# Sheet1.net
KiCad netlist of a schematic drawn in Altium Designer
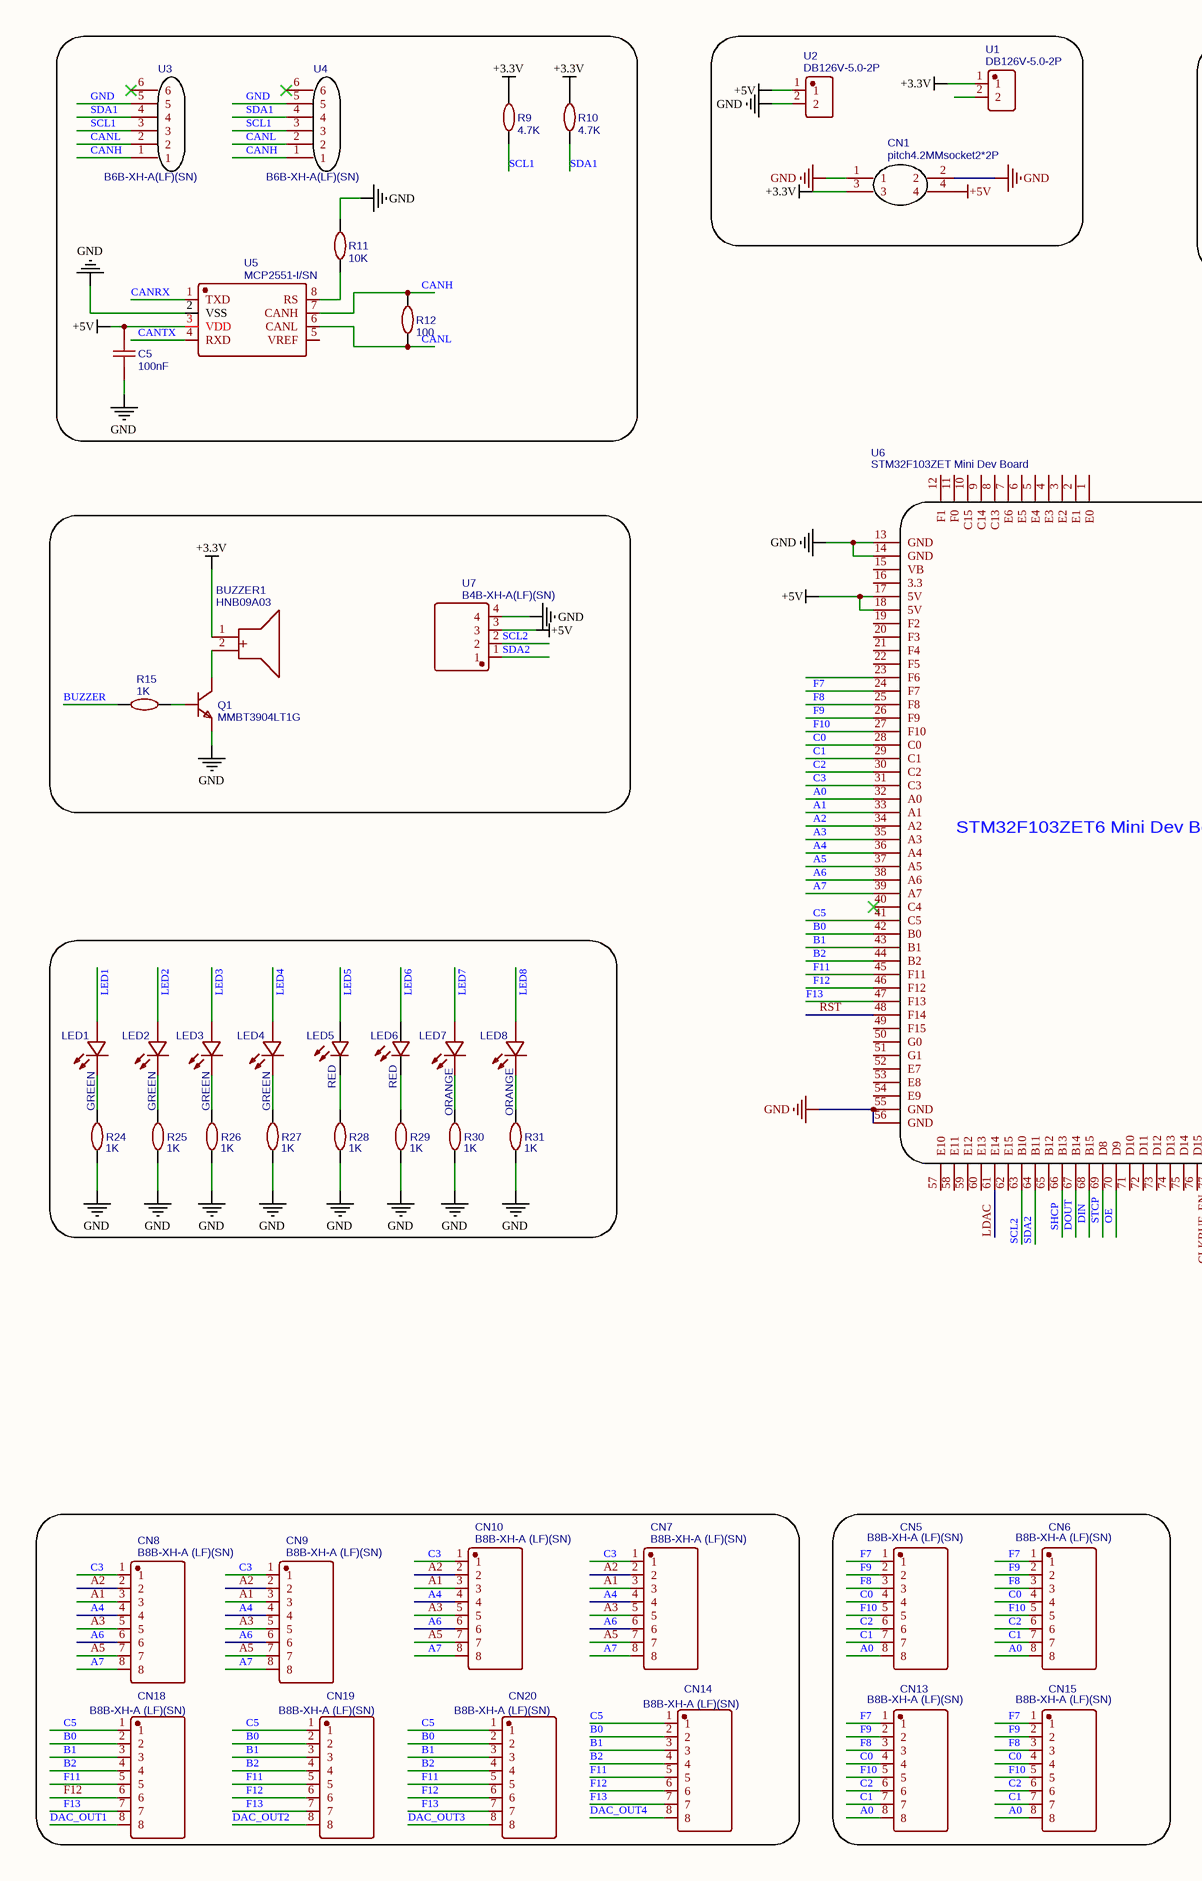
[diagram p0: Sheet1.SchDoc, left]
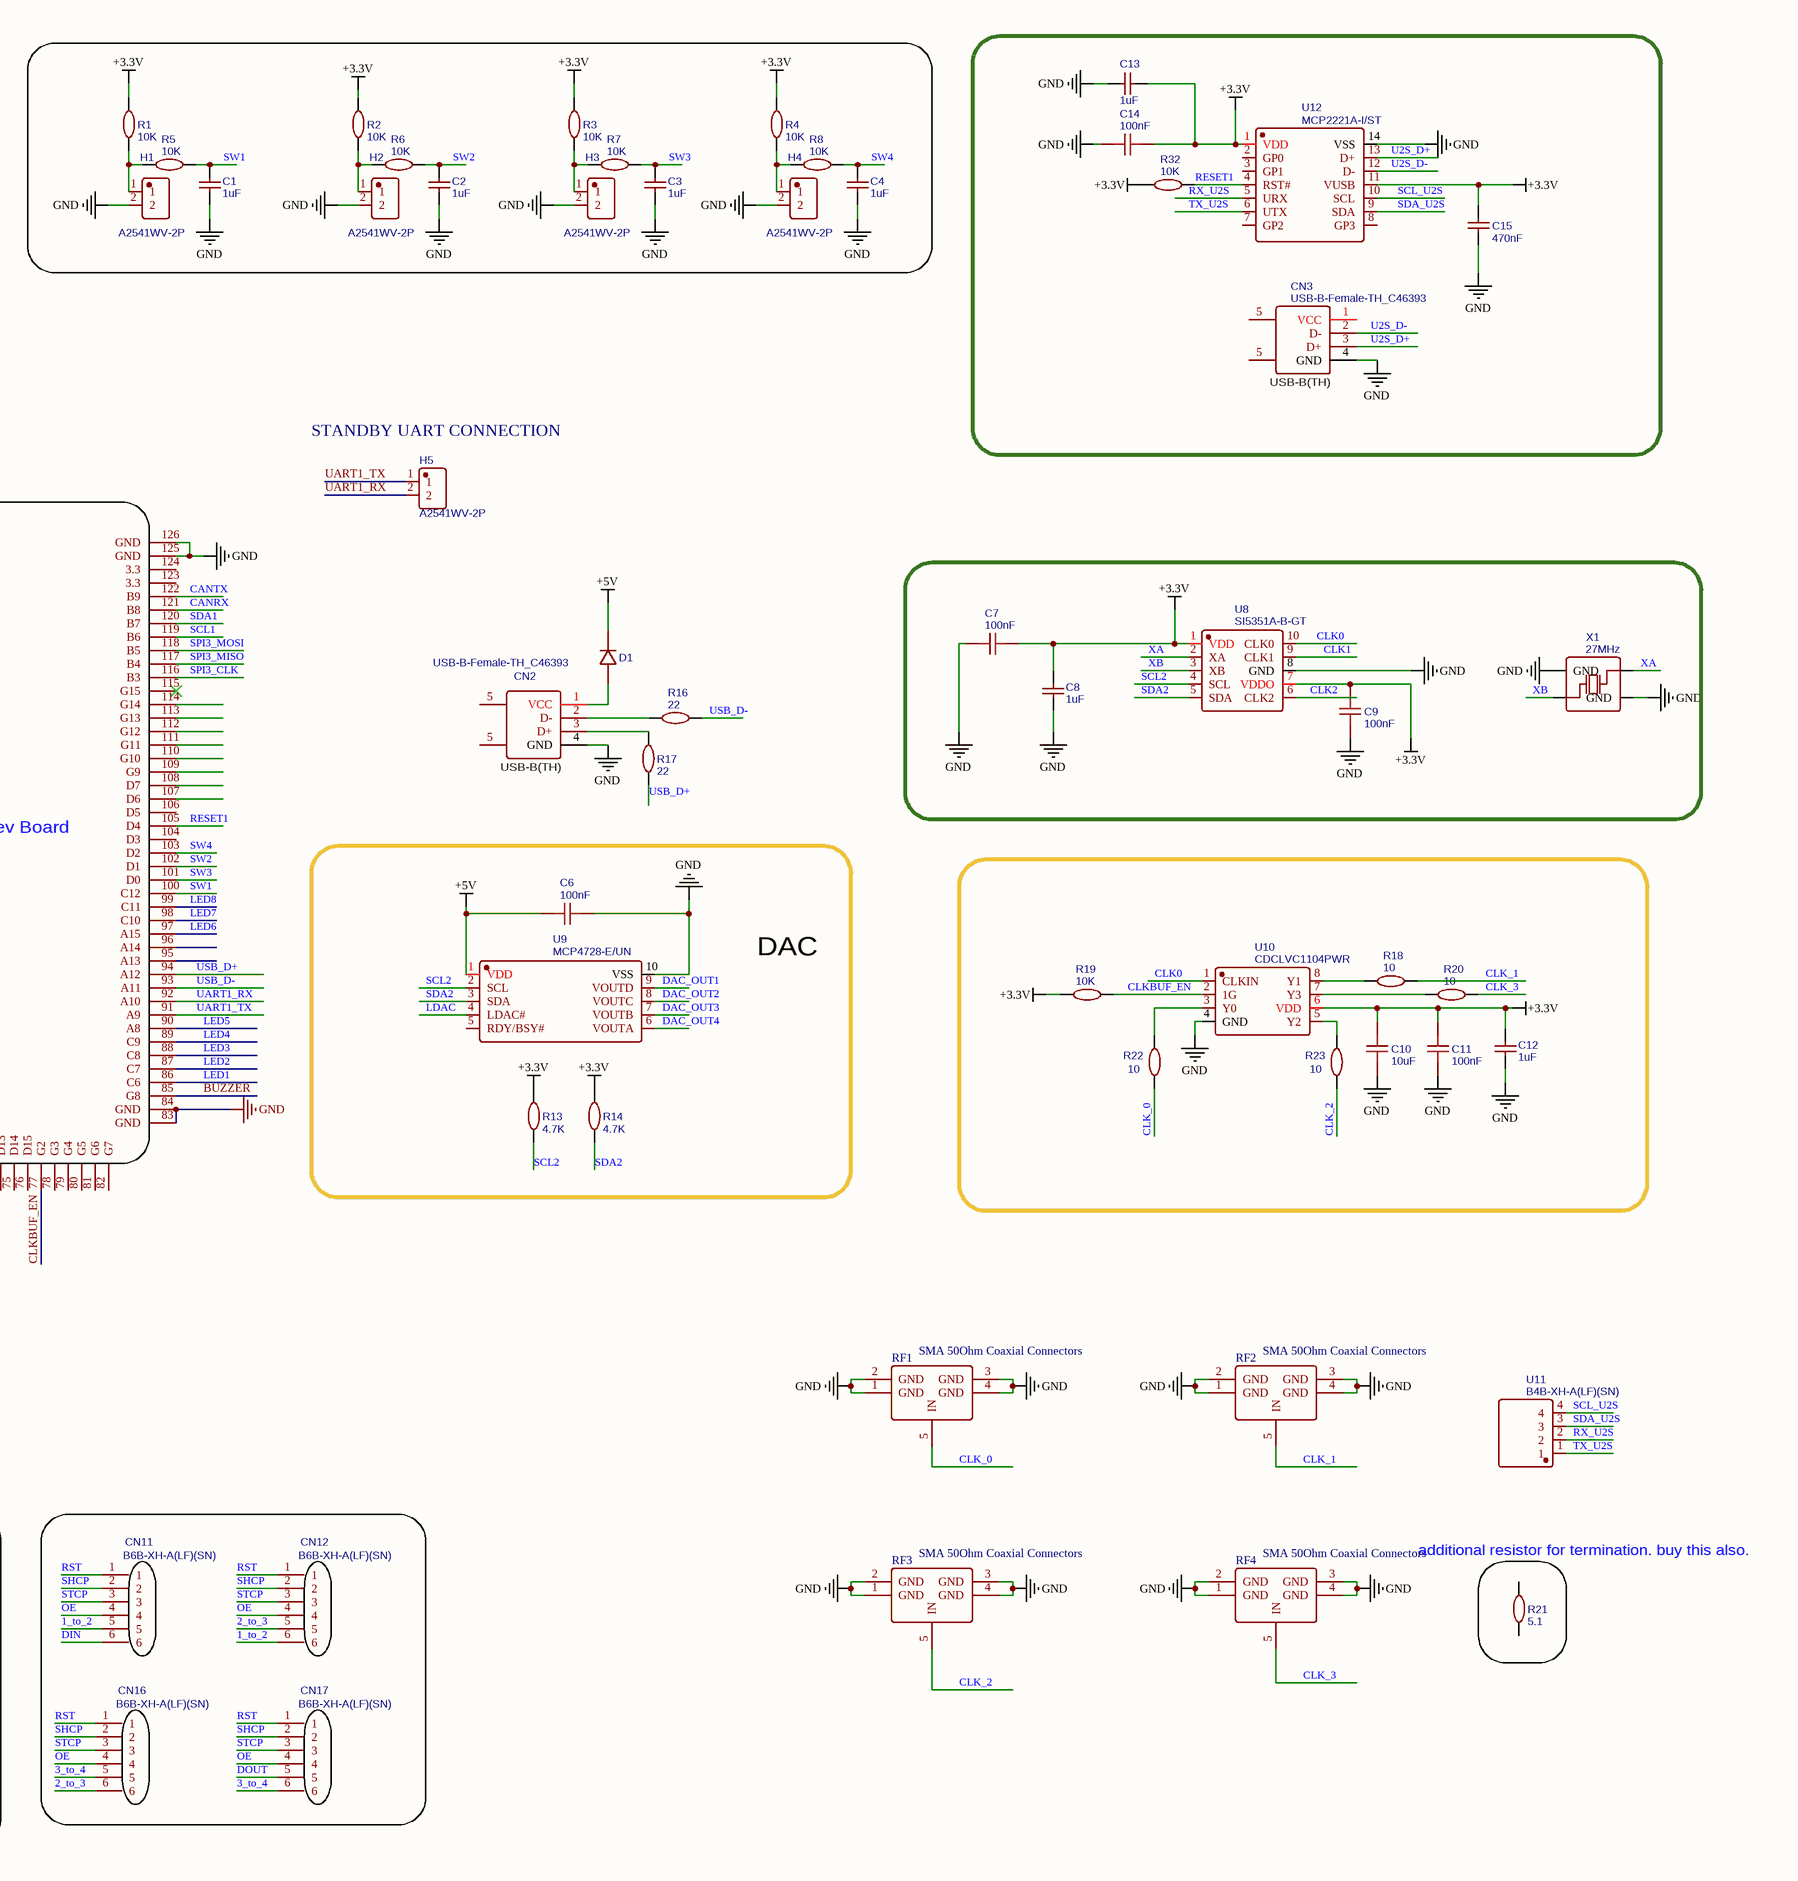
[diagram p1: Sheet1.SchDoc, right]

(export (version "E")
  (design (tool "Eeschema 10.0.6"))
  (components
    (comp (ref "BUZZER1")
      (value "HNB09A03")
      (footprint "BUZ-TH_BD9.0-P5.00-D0.6-FD")
      (fields (field (name "MANUFACTURER") "Jiangsu Huaneng Elec") (field (name "CONTRIBUTOR") "LCSC"))
      (libsource (lib "Main_MCU") (part "HNB09A03"))
    )
    (comp (ref "C1")
      (value "1uF")
      (footprint "C0805")
      (fields
        (field (name "MANUFACTURE PART NUMBER") "CL10A105KP8NNNC")
        (field (name "MANUFACTURER") "SAMSUNG")
      )
      (libsource (lib "Main_MCU") (part "1uF"))
    )
    (comp (ref "C2")
      (value "1uF")
      (footprint "C0805")
      (fields
        (field (name "MANUFACTURE PART NUMBER") "CL10A105KP8NNNC")
        (field (name "MANUFACTURER") "SAMSUNG")
      )
      (libsource (lib "Main_MCU") (part "1uF"))
    )
    (comp (ref "C3")
      (value "1uF")
      (footprint "C0805")
      (fields
        (field (name "MANUFACTURE PART NUMBER") "CL10A105KP8NNNC")
        (field (name "MANUFACTURER") "SAMSUNG")
      )
      (libsource (lib "Main_MCU") (part "1uF"))
    )
    (comp (ref "C4")
      (value "1uF")
      (footprint "C0805")
      (fields
        (field (name "MANUFACTURE PART NUMBER") "CL10A105KP8NNNC")
        (field (name "MANUFACTURER") "SAMSUNG")
      )
      (libsource (lib "Main_MCU") (part "1uF"))
    )
    (comp (ref "C5")
      (value "100nF")
      (footprint "C0603")
      (fields
        (field (name "MANUFACTURER") "YAGEO")
        (field (name "MANUFACTURE PART NUMBER") "CC0603KRX7R9BB104")
      )
      (libsource (lib "Main_MCU") (part "100nF"))
    )
    (comp (ref "C6")
      (value "100nF")
      (footprint "C0603")
      (fields
        (field (name "MANUFACTURER") "YAGEO")
        (field (name "MANUFACTURE PART NUMBER") "CC0603KRX7R9BB104")
      )
      (libsource (lib "Main_MCU") (part "100nF"))
    )
    (comp (ref "C7")
      (value "100nF")
      (footprint "C0603")
      (fields
        (field (name "MANUFACTURER") "YAGEO")
        (field (name "MANUFACTURE PART NUMBER") "CC0603KRX7R9BB104")
      )
      (libsource (lib "Main_MCU") (part "100nF"))
    )
    (comp (ref "C8")
      (value "1uF")
      (footprint "C0805")
      (fields
        (field (name "MANUFACTURE PART NUMBER") "CL10A105KP8NNNC")
        (field (name "MANUFACTURER") "SAMSUNG")
      )
      (libsource (lib "Main_MCU") (part "1uF"))
    )
    (comp (ref "C9")
      (value "100nF")
      (footprint "C0603")
      (fields
        (field (name "MANUFACTURER") "YAGEO")
        (field (name "MANUFACTURE PART NUMBER") "CC0603KRX7R9BB104")
      )
      (libsource (lib "Main_MCU") (part "100nF"))
    )
    (comp (ref "C10")
      (value "10uF")
      (footprint "C0805")
      (fields
        (field (name "MANUFACTURER") "SAMSUNG")
        (field (name "MANUFACTURE PART NUMBER") "CL21B106KOQNNNE")
      )
      (libsource (lib "Main_MCU") (part "10uF"))
    )
    (comp (ref "C11")
      (value "100nF")
      (footprint "C0603")
      (fields
        (field (name "MANUFACTURER") "YAGEO")
        (field (name "MANUFACTURE PART NUMBER") "CC0603KRX7R9BB104")
      )
      (libsource (lib "Main_MCU") (part "100nF"))
    )
    (comp (ref "C12")
      (value "1uF")
      (footprint "C0805")
      (fields
        (field (name "MANUFACTURE PART NUMBER") "CL10A105KP8NNNC")
        (field (name "MANUFACTURER") "SAMSUNG")
      )
      (libsource (lib "Main_MCU") (part "1uF"))
    )
    (comp (ref "C13")
      (value "1uF")
      (footprint "C0805")
      (fields
        (field (name "MANUFACTURE PART NUMBER") "CL10A105KP8NNNC")
        (field (name "MANUFACTURER") "SAMSUNG")
      )
      (libsource (lib "Main_MCU") (part "1uF"))
    )
    (comp (ref "C14")
      (value "100nF")
      (footprint "C0603")
      (fields
        (field (name "MANUFACTURER") "YAGEO")
        (field (name "MANUFACTURE PART NUMBER") "CC0603KRX7R9BB104")
      )
      (libsource (lib "Main_MCU") (part "100nF"))
    )
    (comp (ref "C15")
      (value "470nF")
      (footprint "C0603")
      (fields
        (field (name "MANUFACTURER") "WTC")
        (field (name "MANUFACTURE PART NUMBER") "0603B474K100")
        (field (name "CONTRIBUTOR") "LCSC")
      )
      (libsource (lib "Main_MCU") (part "470nF"))
    )
    (comp (ref "CN1")
      (value "pitch4.2MMsocket2*2P")
      (footprint "CONN-TH_HAA420A-4A")
      (fields (field (name "MANUFACTURER") "BOOMELE"))
      (libsource (lib "Main_MCU") (part "pitch4.2MMsocket2*2P"))
    )
    (comp (ref "CN2")
      (value "USB-B-Female-TH_C46393")
      (footprint "USB-B_TH_BF90")
      (fields
        (field (name "MANUFACTURE PART NUMBER") "C46393")
        (field (name "MANUFACTURER") "Jing Extension of the Electronic Co.")
      )
      (libsource (lib "Main_MCU") (part "USB-B-Female-TH_C46393"))
    )
    (comp (ref "CN3")
      (value "USB-B-Female-TH_C46393")
      (footprint "USB-B_TH_BF90")
      (fields
        (field (name "MANUFACTURE PART NUMBER") "C46393")
        (field (name "MANUFACTURER") "Jing Extension of the Electronic Co.")
      )
      (libsource (lib "Main_MCU") (part "USB-B-Female-TH_C46393"))
    )
    (comp (ref "CN5")
      (value "B8B-XH-A (LF)(SN)")
      (footprint "CONN-TH_B8B-XH-A (LF)(SN)")
      (fields (field (name "MANUFACTURER") "JST Sales America") (field (name "CONTRIBUTOR") "LCSC"))
      (libsource (lib "Main_MCU") (part "B8B-XH-A (LF)(SN)"))
    )
    (comp (ref "CN6")
      (value "B8B-XH-A (LF)(SN)")
      (footprint "CONN-TH_B8B-XH-A (LF)(SN)")
      (fields (field (name "MANUFACTURER") "JST Sales America") (field (name "CONTRIBUTOR") "LCSC"))
      (libsource (lib "Main_MCU") (part "B8B-XH-A (LF)(SN)"))
    )
    (comp (ref "CN7")
      (value "B8B-XH-A (LF)(SN)")
      (footprint "CONN-TH_B8B-XH-A (LF)(SN)")
      (fields (field (name "MANUFACTURER") "JST Sales America") (field (name "CONTRIBUTOR") "LCSC"))
      (libsource (lib "Main_MCU") (part "B8B-XH-A (LF)(SN)"))
    )
    (comp (ref "CN8")
      (value "B8B-XH-A (LF)(SN)")
      (footprint "CONN-TH_B8B-XH-A (LF)(SN)")
      (fields (field (name "MANUFACTURER") "JST Sales America") (field (name "CONTRIBUTOR") "LCSC"))
      (libsource (lib "Main_MCU") (part "B8B-XH-A (LF)(SN)"))
    )
    (comp (ref "CN9")
      (value "B8B-XH-A (LF)(SN)")
      (footprint "CONN-TH_B8B-XH-A (LF)(SN)")
      (fields (field (name "MANUFACTURER") "JST Sales America") (field (name "CONTRIBUTOR") "LCSC"))
      (libsource (lib "Main_MCU") (part "B8B-XH-A (LF)(SN)"))
    )
    (comp (ref "CN10")
      (value "B8B-XH-A (LF)(SN)")
      (footprint "CONN-TH_B8B-XH-A (LF)(SN)")
      (fields (field (name "MANUFACTURER") "JST Sales America") (field (name "CONTRIBUTOR") "LCSC"))
      (libsource (lib "Main_MCU") (part "B8B-XH-A (LF)(SN)"))
    )
    (comp (ref "CN11")
      (value "B6B-XH-A(LF)(SN)")
      (footprint "CONN-TH_6P-P2.50_B6B-XH-A(LF)(SN)")
      (fields (field (name "MANUFACTURER") "JST Sales America") (field (name "CONTRIBUTOR") "LCSC"))
      (libsource (lib "Main_MCU") (part "B6B-XH-A(LF)(SN)"))
    )
    (comp (ref "CN12")
      (value "B6B-XH-A(LF)(SN)")
      (footprint "CONN-TH_6P-P2.50_B6B-XH-A(LF)(SN)")
      (fields (field (name "MANUFACTURER") "JST Sales America") (field (name "CONTRIBUTOR") "LCSC"))
      (libsource (lib "Main_MCU") (part "B6B-XH-A(LF)(SN)"))
    )
    (comp (ref "CN13")
      (value "B8B-XH-A (LF)(SN)")
      (footprint "CONN-TH_B8B-XH-A (LF)(SN)")
      (fields (field (name "MANUFACTURER") "JST Sales America") (field (name "CONTRIBUTOR") "LCSC"))
      (libsource (lib "Main_MCU") (part "B8B-XH-A (LF)(SN)"))
    )
    (comp (ref "CN14")
      (value "B8B-XH-A (LF)(SN)")
      (footprint "CONN-TH_B8B-XH-A (LF)(SN)")
      (fields (field (name "MANUFACTURER") "JST Sales America") (field (name "CONTRIBUTOR") "LCSC"))
      (libsource (lib "Main_MCU") (part "B8B-XH-A (LF)(SN)"))
    )
    (comp (ref "CN15")
      (value "B8B-XH-A (LF)(SN)")
      (footprint "CONN-TH_B8B-XH-A (LF)(SN)")
      (fields (field (name "MANUFACTURER") "JST Sales America") (field (name "CONTRIBUTOR") "LCSC"))
      (libsource (lib "Main_MCU") (part "B8B-XH-A (LF)(SN)"))
    )
    (comp (ref "CN16")
      (value "B6B-XH-A(LF)(SN)")
      (footprint "CONN-TH_6P-P2.50_B6B-XH-A(LF)(SN)")
      (fields (field (name "MANUFACTURER") "JST Sales America") (field (name "CONTRIBUTOR") "LCSC"))
      (libsource (lib "Main_MCU") (part "B6B-XH-A(LF)(SN)"))
    )
    (comp (ref "CN17")
      (value "B6B-XH-A(LF)(SN)")
      (footprint "CONN-TH_6P-P2.50_B6B-XH-A(LF)(SN)")
      (fields (field (name "MANUFACTURER") "JST Sales America") (field (name "CONTRIBUTOR") "LCSC"))
      (libsource (lib "Main_MCU") (part "B6B-XH-A(LF)(SN)"))
    )
    (comp (ref "CN18")
      (value "B8B-XH-A (LF)(SN)")
      (footprint "CONN-TH_B8B-XH-A (LF)(SN)")
      (fields (field (name "MANUFACTURER") "JST Sales America") (field (name "CONTRIBUTOR") "LCSC"))
      (libsource (lib "Main_MCU") (part "B8B-XH-A (LF)(SN)"))
    )
    (comp (ref "CN19")
      (value "B8B-XH-A (LF)(SN)")
      (footprint "CONN-TH_B8B-XH-A (LF)(SN)")
      (fields (field (name "MANUFACTURER") "JST Sales America") (field (name "CONTRIBUTOR") "LCSC"))
      (libsource (lib "Main_MCU") (part "B8B-XH-A (LF)(SN)"))
    )
    (comp (ref "CN20")
      (value "B8B-XH-A (LF)(SN)")
      (footprint "CONN-TH_B8B-XH-A (LF)(SN)")
      (fields (field (name "MANUFACTURER") "JST Sales America") (field (name "CONTRIBUTOR") "LCSC"))
      (libsource (lib "Main_MCU") (part "B8B-XH-A (LF)(SN)"))
    )
    (comp (ref "D1")
      (value "CUS08F30,H3F")
      (footprint "SOD-323F_L2.0-W1.6-LS2.5-RD")
      (fields (field (name "MANUFACTURER") "TOSHIBA") (field (name "CONTRIBUTOR") "LCSC"))
      (libsource (lib "Main_MCU") (part "CUS08F30,H3F"))
    )
    (comp (ref "H1")
      (value "A2541WV-2P")
      (footprint "HDR-TH_P2.54-H-M_A2541WV-2P")
      (fields (field (name "MANUFACTURER") "CJT(Changjiang Connectors)") (field (name "CONTRIBUTOR") "LCSC"))
      (libsource (lib "Main_MCU") (part "A2541WV-2P"))
    )
    (comp (ref "H2")
      (value "A2541WV-2P")
      (footprint "HDR-TH_P2.54-H-M_A2541WV-2P")
      (fields (field (name "MANUFACTURER") "CJT(Changjiang Connectors)") (field (name "CONTRIBUTOR") "LCSC"))
      (libsource (lib "Main_MCU") (part "A2541WV-2P"))
    )
    (comp (ref "H3")
      (value "A2541WV-2P")
      (footprint "HDR-TH_P2.54-H-M_A2541WV-2P")
      (fields (field (name "MANUFACTURER") "CJT(Changjiang Connectors)") (field (name "CONTRIBUTOR") "LCSC"))
      (libsource (lib "Main_MCU") (part "A2541WV-2P"))
    )
    (comp (ref "H4")
      (value "A2541WV-2P")
      (footprint "HDR-TH_P2.54-H-M_A2541WV-2P")
      (fields (field (name "MANUFACTURER") "CJT(Changjiang Connectors)") (field (name "CONTRIBUTOR") "LCSC"))
      (libsource (lib "Main_MCU") (part "A2541WV-2P"))
    )
    (comp (ref "H5")
      (value "A2541WV-2P")
      (footprint "HDR-TH_P2.54-H-M_A2541WV-2P")
      (fields (field (name "MANUFACTURER") "CJT(Changjiang Connectors)") (field (name "CONTRIBUTOR") "LCSC"))
      (libsource (lib "Main_MCU") (part "A2541WV-2P"))
    )
    (comp (ref "LED1")
      (value "GREEN")
      (footprint "LED0603-R-RD")
      (fields
        (field (name "MANUFACTURER") "Orient")
        (field (name "MANUFACTURE PART NUMBER") "ORH-G36G")
        (field (name "CONTRIBUTOR") "LCSC")
      )
      (libsource (lib "Main_MCU") (part "GREEN"))
    )
    (comp (ref "LED2")
      (value "GREEN")
      (footprint "LED0603-R-RD")
      (fields
        (field (name "MANUFACTURER") "Orient")
        (field (name "MANUFACTURE PART NUMBER") "ORH-G36G")
        (field (name "CONTRIBUTOR") "LCSC")
      )
      (libsource (lib "Main_MCU") (part "GREEN"))
    )
    (comp (ref "LED3")
      (value "GREEN")
      (footprint "LED0603-R-RD")
      (fields
        (field (name "MANUFACTURER") "Orient")
        (field (name "MANUFACTURE PART NUMBER") "ORH-G36G")
        (field (name "CONTRIBUTOR") "LCSC")
      )
      (libsource (lib "Main_MCU") (part "GREEN"))
    )
    (comp (ref "LED4")
      (value "GREEN")
      (footprint "LED0603-R-RD")
      (fields
        (field (name "MANUFACTURER") "Orient")
        (field (name "MANUFACTURE PART NUMBER") "ORH-G36G")
        (field (name "CONTRIBUTOR") "LCSC")
      )
      (libsource (lib "Main_MCU") (part "GREEN"))
    )
    (comp (ref "LED5")
      (value "RED")
      (footprint "LED0603-R-RD")
      (fields
        (field (name "MANUFACTURER") "EVERLIGHT")
        (field (name "MANUFACTURE PART NUMBER") "19-217/R6C-AL1M2VY/3T")
      )
      (libsource (lib "Main_MCU") (part "RED"))
    )
    (comp (ref "LED6")
      (value "RED")
      (footprint "LED0603-R-RD")
      (fields
        (field (name "MANUFACTURER") "EVERLIGHT")
        (field (name "MANUFACTURE PART NUMBER") "19-217/R6C-AL1M2VY/3T")
      )
      (libsource (lib "Main_MCU") (part "RED"))
    )
    (comp (ref "LED7")
      (value "ORANGE")
      (footprint "LED0603-R-RD")
      (fields
        (field (name "MANUFACTURER") "Orient")
        (field (name "MANUFACTURE PART NUMBER") "ORH-R36A(0.6T)")
        (field (name "CONTRIBUTOR") "LCSC")
      )
      (libsource (lib "Main_MCU") (part "ORANGE"))
    )
    (comp (ref "LED8")
      (value "ORANGE")
      (footprint "LED0603-R-RD")
      (fields
        (field (name "MANUFACTURER") "Orient")
        (field (name "MANUFACTURE PART NUMBER") "ORH-R36A(0.6T)")
        (field (name "CONTRIBUTOR") "LCSC")
      )
      (libsource (lib "Main_MCU") (part "ORANGE"))
    )
    (comp (ref "Q1")
      (value "MMBT3904LT1G")
      (footprint "SOT-23-3_L2.9-W1.6-P1.90-LS2.8-BR")
      (fields (field (name "MANUFACTURER") "ON"))
      (libsource (lib "Main_MCU") (part "MMBT3904LT1G"))
    )
    (comp (ref "R1")
      (value "10K")
      (footprint "R0603")
      (fields
        (field (name "MANUFACTURER") "YAGEO")
        (field (name "MANUFACTURE PART NUMBER") "RC0603FR-0710KL")
      )
      (libsource (lib "Main_MCU") (part "10K"))
    )
    (comp (ref "R2")
      (value "10K")
      (footprint "R0603")
      (fields
        (field (name "MANUFACTURER") "YAGEO")
        (field (name "MANUFACTURE PART NUMBER") "RC0603FR-0710KL")
      )
      (libsource (lib "Main_MCU") (part "10K"))
    )
    (comp (ref "R3")
      (value "10K")
      (footprint "R0603")
      (fields
        (field (name "MANUFACTURER") "YAGEO")
        (field (name "MANUFACTURE PART NUMBER") "RC0603FR-0710KL")
      )
      (libsource (lib "Main_MCU") (part "10K"))
    )
    (comp (ref "R4")
      (value "10K")
      (footprint "R0603")
      (fields
        (field (name "MANUFACTURER") "YAGEO")
        (field (name "MANUFACTURE PART NUMBER") "RC0603FR-0710KL")
      )
      (libsource (lib "Main_MCU") (part "10K"))
    )
    (comp (ref "R5")
      (value "10K")
      (footprint "R0603")
      (fields
        (field (name "MANUFACTURER") "YAGEO")
        (field (name "MANUFACTURE PART NUMBER") "RC0603FR-0710KL")
      )
      (libsource (lib "Main_MCU") (part "10K"))
    )
    (comp (ref "R6")
      (value "10K")
      (footprint "R0603")
      (fields
        (field (name "MANUFACTURER") "YAGEO")
        (field (name "MANUFACTURE PART NUMBER") "RC0603FR-0710KL")
      )
      (libsource (lib "Main_MCU") (part "10K"))
    )
    (comp (ref "R7")
      (value "10K")
      (footprint "R0603")
      (fields
        (field (name "MANUFACTURER") "YAGEO")
        (field (name "MANUFACTURE PART NUMBER") "RC0603FR-0710KL")
      )
      (libsource (lib "Main_MCU") (part "10K"))
    )
    (comp (ref "R8")
      (value "10K")
      (footprint "R0603")
      (fields
        (field (name "MANUFACTURER") "YAGEO")
        (field (name "MANUFACTURE PART NUMBER") "RC0603FR-0710KL")
      )
      (libsource (lib "Main_MCU") (part "10K"))
    )
    (comp (ref "R9")
      (value "4.7K")
      (footprint "R0603")
      (fields
        (field (name "MANUFACTURER") "YAGEO")
        (field (name "MANUFACTURE PART NUMBER") "RC0603FR-074K7L")
      )
      (libsource (lib "Main_MCU") (part "4.7K"))
    )
    (comp (ref "R10")
      (value "4.7K")
      (footprint "R0603")
      (fields
        (field (name "MANUFACTURER") "YAGEO")
        (field (name "MANUFACTURE PART NUMBER") "RC0603FR-074K7L")
      )
      (libsource (lib "Main_MCU") (part "4.7K"))
    )
    (comp (ref "R11")
      (value "10K")
      (footprint "R0603")
      (fields
        (field (name "MANUFACTURER") "YAGEO")
        (field (name "MANUFACTURE PART NUMBER") "RC0603FR-0710KL")
      )
      (libsource (lib "Main_MCU") (part "10K"))
    )
    (comp (ref "R12")
      (value "100")
      (footprint "R0603")
      (fields
        (field (name "MANUFACTURER") "UniOhm")
        (field (name "MANUFACTURE PART NUMBER") "0603WAF1000T5E")
      )
      (libsource (lib "Main_MCU") (part "100"))
    )
    (comp (ref "R13")
      (value "4.7K")
      (footprint "R0603")
      (fields
        (field (name "MANUFACTURER") "YAGEO")
        (field (name "MANUFACTURE PART NUMBER") "RC0603FR-074K7L")
      )
      (libsource (lib "Main_MCU") (part "4.7K"))
    )
    (comp (ref "R14")
      (value "4.7K")
      (footprint "R0603")
      (fields
        (field (name "MANUFACTURER") "YAGEO")
        (field (name "MANUFACTURE PART NUMBER") "RC0603FR-074K7L")
      )
      (libsource (lib "Main_MCU") (part "4.7K"))
    )
    (comp (ref "R15")
      (value "1K")
      (footprint "R0603")
      (fields (field (name "MANUFACTURE PART NUMBER") "RC0603FR-071KL") (field (name "MANUFACTURER") "YAGEO"))
      (libsource (lib "Main_MCU") (part "1K"))
    )
    (comp (ref "R16")
      (value "22")
      (footprint "R0603")
      (fields
        (field (name "MANUFACTURER") "UniOhm")
        (field (name "MANUFACTURE PART NUMBER") "0603WAJ0220T5E")
      )
      (libsource (lib "Main_MCU") (part "22"))
    )
    (comp (ref "R17")
      (value "22")
      (footprint "R0603")
      (fields
        (field (name "MANUFACTURER") "UniOhm")
        (field (name "MANUFACTURE PART NUMBER") "0603WAJ0220T5E")
      )
      (libsource (lib "Main_MCU") (part "22"))
    )
    (comp (ref "R18")
      (value "10")
      (footprint "R0603")
      (fields
        (field (name "MANUFACTURER") "YAGEO")
        (field (name "MANUFACTURE PART NUMBER") "RC0603FR-0710RL")
      )
      (libsource (lib "Main_MCU") (part "10"))
    )
    (comp (ref "R19")
      (value "10K")
      (footprint "R0603")
      (fields
        (field (name "MANUFACTURER") "YAGEO")
        (field (name "MANUFACTURE PART NUMBER") "RC0603FR-0710KL")
      )
      (libsource (lib "Main_MCU") (part "10K"))
    )
    (comp (ref "R20")
      (value "10")
      (footprint "R0603")
      (fields
        (field (name "MANUFACTURER") "YAGEO")
        (field (name "MANUFACTURE PART NUMBER") "RC0603FR-0710RL")
      )
      (libsource (lib "Main_MCU") (part "10"))
    )
    (comp (ref "R21")
      (value "5.1")
      (footprint "R0603")
      (fields
        (field (name "MANUFACTURER") "UniOhm")
        (field (name "MANUFACTURE PART NUMBER") "0603WAF510KT5E")
      )
      (libsource (lib "Main_MCU") (part "5.1"))
    )
    (comp (ref "R22")
      (value "10")
      (footprint "R0603")
      (fields
        (field (name "MANUFACTURER") "YAGEO")
        (field (name "MANUFACTURE PART NUMBER") "RC0603FR-0710RL")
      )
      (libsource (lib "Main_MCU") (part "10"))
    )
    (comp (ref "R23")
      (value "10")
      (footprint "R0603")
      (fields
        (field (name "MANUFACTURER") "YAGEO")
        (field (name "MANUFACTURE PART NUMBER") "RC0603FR-0710RL")
      )
      (libsource (lib "Main_MCU") (part "10"))
    )
    (comp (ref "R24")
      (value "1K")
      (footprint "R0603")
      (fields (field (name "MANUFACTURE PART NUMBER") "RC0603FR-071KL") (field (name "MANUFACTURER") "YAGEO"))
      (libsource (lib "Main_MCU") (part "1K"))
    )
    (comp (ref "R25")
      (value "1K")
      (footprint "R0603")
      (fields (field (name "MANUFACTURE PART NUMBER") "RC0603FR-071KL") (field (name "MANUFACTURER") "YAGEO"))
      (libsource (lib "Main_MCU") (part "1K"))
    )
    (comp (ref "R26")
      (value "1K")
      (footprint "R0603")
      (fields (field (name "MANUFACTURE PART NUMBER") "RC0603FR-071KL") (field (name "MANUFACTURER") "YAGEO"))
      (libsource (lib "Main_MCU") (part "1K"))
    )
    (comp (ref "R27")
      (value "1K")
      (footprint "R0603")
      (fields (field (name "MANUFACTURE PART NUMBER") "RC0603FR-071KL") (field (name "MANUFACTURER") "YAGEO"))
      (libsource (lib "Main_MCU") (part "1K"))
    )
    (comp (ref "R28")
      (value "1K")
      (footprint "R0603")
      (fields (field (name "MANUFACTURE PART NUMBER") "RC0603FR-071KL") (field (name "MANUFACTURER") "YAGEO"))
      (libsource (lib "Main_MCU") (part "1K"))
    )
    (comp (ref "R29")
      (value "1K")
      (footprint "R0603")
      (fields (field (name "MANUFACTURE PART NUMBER") "RC0603FR-071KL") (field (name "MANUFACTURER") "YAGEO"))
      (libsource (lib "Main_MCU") (part "1K"))
    )
    (comp (ref "R30")
      (value "1K")
      (footprint "R0603")
      (fields (field (name "MANUFACTURE PART NUMBER") "RC0603FR-071KL") (field (name "MANUFACTURER") "YAGEO"))
      (libsource (lib "Main_MCU") (part "1K"))
    )
    (comp (ref "R31")
      (value "1K")
      (footprint "R0603")
      (fields (field (name "MANUFACTURE PART NUMBER") "RC0603FR-071KL") (field (name "MANUFACTURER") "YAGEO"))
      (libsource (lib "Main_MCU") (part "1K"))
    )
    (comp (ref "R32")
      (value "10K")
      (footprint "R0603")
      (fields
        (field (name "MANUFACTURER") "YAGEO")
        (field (name "MANUFACTURE PART NUMBER") "RC0603FR-0710KL")
      )
      (libsource (lib "Main_MCU") (part "10K"))
    )
    (comp (ref "RF1")
      (value "SMA 50Ohm Coaxial Connectors")
      (footprint "BWSMA-KE-Z001")
      (fields
        (field (name "MANUFACTURER") "BAT WIRELESS")
        (field (name "MANUFACTURE PART NUMBER") "BWSMA-KE-Z001")
      )
      (libsource (lib "Main_MCU") (part "BWSMA-KE-Z001"))
    )
    (comp (ref "RF2")
      (value "SMA 50Ohm Coaxial Connectors")
      (footprint "BWSMA-KE-Z001")
      (fields
        (field (name "MANUFACTURER") "BAT WIRELESS")
        (field (name "MANUFACTURE PART NUMBER") "BWSMA-KE-Z001")
      )
      (libsource (lib "Main_MCU") (part "BWSMA-KE-Z001"))
    )
    (comp (ref "RF3")
      (value "SMA 50Ohm Coaxial Connectors")
      (footprint "BWSMA-KE-Z001")
      (fields
        (field (name "MANUFACTURER") "BAT WIRELESS")
        (field (name "MANUFACTURE PART NUMBER") "BWSMA-KE-Z001")
      )
      (libsource (lib "Main_MCU") (part "BWSMA-KE-Z001"))
    )
    (comp (ref "RF4")
      (value "SMA 50Ohm Coaxial Connectors")
      (footprint "BWSMA-KE-Z001")
      (fields
        (field (name "MANUFACTURER") "BAT WIRELESS")
        (field (name "MANUFACTURE PART NUMBER") "BWSMA-KE-Z001")
      )
      (libsource (lib "Main_MCU") (part "BWSMA-KE-Z001"))
    )
    (comp (ref "U1")
      (value "DB126V-5.0-2P")
      (footprint "CONN-TH_2P-P5.00_L7.8-W10.0")
      (fields (field (name "MANUFACTURER") "DIBO") (field (name "CONTRIBUTOR") "LCSC"))
      (libsource (lib "Main_MCU") (part "DB126V-5.0-2P"))
    )
    (comp (ref "U2")
      (value "DB126V-5.0-2P")
      (footprint "CONN-TH_2P-P5.00_L7.8-W10.0")
      (fields (field (name "MANUFACTURER") "DIBO") (field (name "CONTRIBUTOR") "LCSC"))
      (libsource (lib "Main_MCU") (part "DB126V-5.0-2P"))
    )
    (comp (ref "U3")
      (value "B6B-XH-A(LF)(SN)")
      (footprint "CONN-TH_6P-P2.50_B6B-XH-A(LF)(SN)")
      (fields (field (name "MANUFACTURER") "JST Sales America") (field (name "CONTRIBUTOR") "LCSC"))
      (libsource (lib "Main_MCU") (part "B6B-XH-A(LF)(SN)"))
    )
    (comp (ref "U4")
      (value "B6B-XH-A(LF)(SN)")
      (footprint "CONN-TH_6P-P2.50_B6B-XH-A(LF)(SN)")
      (fields (field (name "MANUFACTURER") "JST Sales America") (field (name "CONTRIBUTOR") "LCSC"))
      (libsource (lib "Main_MCU") (part "B6B-XH-A(LF)(SN)"))
    )
    (comp (ref "U5")
      (value "MCP2551-I/SN")
      (footprint "SOIC-8_L4.9-W3.9-P1.27-LS6.0-BL")
      (fields (field (name "MANUFACTURER") "MICROCHIP"))
      (libsource (lib "Main_MCU") (part "MCP2551-I/SN"))
    )
    (comp (ref "U6")
      (value "STM32F103ZET Mini Dev Board")
      (footprint "STM32F103ZET MINI DEV BOARD")
      (fields (field (name "CONTRIBUTOR") "FYP_Squad"))
      (libsource (lib "Main_MCU") (part "STM32F103ZET Mini Dev Board"))
    )
    (comp (ref "U7")
      (value "B4B-XH-A(LF)(SN)")
      (footprint "CONN-TH_B4B-XH-A (LF)(SN)")
      (fields (field (name "MANUFACTURER") "JST Sales America") (field (name "CONTRIBUTOR") "LCSC"))
      (libsource (lib "Main_MCU") (part "B4B-XH-A(LF)(SN)"))
    )
    (comp (ref "U8")
      (value "SI5351A-B-GT")
      (footprint "MSOP-10_L3.0-W3.0-P0.50-LS5.0-BL")
      (fields (field (name "MANUFACTURER") "SILICON LABS") (field (name "CONTRIBUTOR") "LCSC"))
      (libsource (lib "Main_MCU") (part "SI5351A-B-GT"))
    )
    (comp (ref "U9")
      (value "MCP4728-E/UN")
      (footprint "MSOP-10_L3.0-W3.0-P0.50-LS5.0-TL")
      (fields (field (name "MANUFACTURER") "Microchip Tech") (field (name "CONTRIBUTOR") "LCSC"))
      (libsource (lib "Main_MCU") (part "MCP4728-E/UN"))
    )
    (comp (ref "U10")
      (value "CDCLVC1104PWR")
      (footprint "TSSOP-8_L4.4-W3.0-P0.65-LS6.4-BL")
      (fields (field (name "MANUFACTURER") "Texas Instruments") (field (name "CONTRIBUTOR") "LCSC"))
      (libsource (lib "Main_MCU") (part "CDCLVC1104PWR"))
    )
    (comp (ref "U11")
      (value "B4B-XH-A(LF)(SN)")
      (footprint "CONN-TH_B4B-XH-A (LF)(SN)")
      (fields (field (name "MANUFACTURER") "JST Sales America") (field (name "CONTRIBUTOR") "LCSC"))
      (libsource (lib "Main_MCU") (part "B4B-XH-A(LF)(SN)"))
    )
    (comp (ref "U12")
      (value "MCP2221A-I/ST")
      (footprint "TSSOP-14_L5.0-W4.4-P0.65-LS6.4-BL")
      (fields (field (name "MANUFACTURER") "MICROCHIP") (field (name "CONTRIBUTOR") "LCSC"))
      (libsource (lib "Main_MCU") (part "MCP2221A-I/ST"))
    )
    (comp (ref "X1")
      (value "27MHz")
      (footprint "OSC-SMD_4P-L2.5-W2.0-BL")
      (fields
        (field (name "MANUFACTURER") "Seiko Epson")
        (field (name "MANUFACTURE PART NUMBER") "Q24FA20H00238")
        (field (name "CONTRIBUTOR") "LCSC")
      )
      (libsource (lib "Main_MCU") (part "27MHz"))
    )
  )
  (nets
    (net (code "1") (name "+3.3V") (class "Default")
      (node (ref "BUZZER1") (pin "1") (pinfunction "+_1") (pintype "passive"))
      (node (ref "C10") (pin "2") (pinfunction "2_2") (pintype "passive"))
      (node (ref "C11") (pin "2") (pinfunction "2_2") (pintype "passive"))
      (node (ref "C12") (pin "2") (pinfunction "2_2") (pintype "passive"))
      (node (ref "C13") (pin "1") (pinfunction "1_1") (pintype "passive"))
      (node (ref "C14") (pin "2") (pinfunction "2_2") (pintype "passive"))
      (node (ref "C15") (pin "2") (pinfunction "2_2") (pintype "passive"))
      (node (ref "C7") (pin "2") (pinfunction "2_2") (pintype "passive"))
      (node (ref "C8") (pin "2") (pinfunction "2_2") (pintype "passive"))
      (node (ref "C9") (pin "2") (pinfunction "2_2") (pintype "passive"))
      (node (ref "CN1") (pin "3") (pinfunction "3_3") (pintype "passive"))
      (node (ref "R1") (pin "2") (pinfunction "2_2") (pintype "passive"))
      (node (ref "R10") (pin "2") (pinfunction "2_2") (pintype "passive"))
      (node (ref "R13") (pin "2") (pinfunction "2_2") (pintype "passive"))
      (node (ref "R14") (pin "2") (pinfunction "2_2") (pintype "passive"))
      (node (ref "R19") (pin "2") (pinfunction "2_2") (pintype "passive"))
      (node (ref "R2") (pin "2") (pinfunction "2_2") (pintype "passive"))
      (node (ref "R3") (pin "2") (pinfunction "2_2") (pintype "passive"))
      (node (ref "R32") (pin "1") (pinfunction "1_1") (pintype "passive"))
      (node (ref "R4") (pin "2") (pinfunction "2_2") (pintype "passive"))
      (node (ref "R9") (pin "2") (pinfunction "2_2") (pintype "passive"))
      (node (ref "U1") (pin "1") (pinfunction "1_1") (pintype "passive"))
      (node (ref "U10") (pin "6") (pinfunction "VDD_6") (pintype "passive"))
      (node (ref "U12") (pin "1") (pinfunction "VDD_1") (pintype "passive"))
      (node (ref "U12") (pin "11") (pinfunction "VUSB_11") (pintype "passive"))
      (node (ref "U8") (pin "1") (pinfunction "VDD_1") (pintype "passive"))
      (node (ref "U8") (pin "7") (pinfunction "VDDO_7") (pintype "passive"))
    )
    (net (code "2") (name "+5V") (class "Default")
      (node (ref "C5") (pin "2") (pinfunction "2_2") (pintype "passive"))
      (node (ref "C6") (pin "1") (pinfunction "1_1") (pintype "passive"))
      (node (ref "CN1") (pin "4") (pinfunction "4_4") (pintype "passive"))
      (node (ref "D1") (pin "1") (pinfunction "C_1") (pintype "passive"))
      (node (ref "U2") (pin "1") (pinfunction "1_1") (pintype "passive"))
      (node (ref "U5") (pin "3") (pinfunction "VDD_3") (pintype "passive"))
      (node (ref "U6") (pin "17") (pinfunction "5V_17") (pintype "passive"))
      (node (ref "U6") (pin "18") (pinfunction "5V_18") (pintype "passive"))
      (node (ref "U7") (pin "3") (pinfunction "3_3") (pintype "passive"))
      (node (ref "U9") (pin "1") (pinfunction "VDD_1") (pintype "passive"))
    )
    (net (code "3") (name "/1_to_2") (class "Default")
      (node (ref "CN11") (pin "5") (pinfunction "5_5") (pintype "passive"))
      (node (ref "CN12") (pin "6") (pinfunction "6_6") (pintype "passive"))
    )
    (net (code "4") (name "/2_to_3") (class "Default")
      (node (ref "CN12") (pin "5") (pinfunction "5_5") (pintype "passive"))
      (node (ref "CN16") (pin "6") (pinfunction "6_6") (pintype "passive"))
    )
    (net (code "5") (name "/3_to_4") (class "Default")
      (node (ref "CN16") (pin "5") (pinfunction "5_5") (pintype "passive"))
      (node (ref "CN17") (pin "6") (pinfunction "6_6") (pintype "passive"))
    )
    (net (code "6") (name "/A0") (class "Default")
      (node (ref "CN13") (pin "8") (pinfunction "8_8") (pintype "passive"))
      (node (ref "CN15") (pin "8") (pinfunction "8_8") (pintype "passive"))
      (node (ref "CN5") (pin "8") (pinfunction "8_8") (pintype "passive"))
      (node (ref "CN6") (pin "8") (pinfunction "8_8") (pintype "passive"))
      (node (ref "U6") (pin "32") (pinfunction "A0_32") (pintype "passive"))
    )
    (net (code "7") (name "/A1") (class "Default")
      (node (ref "CN10") (pin "3") (pinfunction "3_3") (pintype "passive"))
      (node (ref "CN7") (pin "3") (pinfunction "3_3") (pintype "passive"))
      (node (ref "CN8") (pin "3") (pinfunction "3_3") (pintype "passive"))
      (node (ref "CN9") (pin "3") (pinfunction "3_3") (pintype "passive"))
      (node (ref "U6") (pin "33") (pinfunction "A1_33") (pintype "passive"))
    )
    (net (code "8") (name "/A2") (class "Default")
      (node (ref "CN10") (pin "2") (pinfunction "2_2") (pintype "passive"))
      (node (ref "CN7") (pin "2") (pinfunction "2_2") (pintype "passive"))
      (node (ref "CN8") (pin "2") (pinfunction "2_2") (pintype "passive"))
      (node (ref "CN9") (pin "2") (pinfunction "2_2") (pintype "passive"))
      (node (ref "U6") (pin "34") (pinfunction "A2_34") (pintype "passive"))
    )
    (net (code "9") (name "/A3") (class "Default")
      (node (ref "CN10") (pin "5") (pinfunction "5_5") (pintype "passive"))
      (node (ref "CN7") (pin "5") (pinfunction "5_5") (pintype "passive"))
      (node (ref "CN8") (pin "5") (pinfunction "5_5") (pintype "passive"))
      (node (ref "CN9") (pin "5") (pinfunction "5_5") (pintype "passive"))
      (node (ref "U6") (pin "35") (pinfunction "A3_35") (pintype "passive"))
    )
    (net (code "10") (name "/A4") (class "Default")
      (node (ref "CN10") (pin "4") (pinfunction "4_4") (pintype "passive"))
      (node (ref "CN7") (pin "4") (pinfunction "4_4") (pintype "passive"))
      (node (ref "CN8") (pin "4") (pinfunction "4_4") (pintype "passive"))
      (node (ref "CN9") (pin "4") (pinfunction "4_4") (pintype "passive"))
      (node (ref "U6") (pin "36") (pinfunction "A4_36") (pintype "passive"))
    )
    (net (code "11") (name "/A5") (class "Default")
      (node (ref "CN10") (pin "7") (pinfunction "7_7") (pintype "passive"))
      (node (ref "CN7") (pin "7") (pinfunction "7_7") (pintype "passive"))
      (node (ref "CN8") (pin "7") (pinfunction "7_7") (pintype "passive"))
      (node (ref "CN9") (pin "7") (pinfunction "7_7") (pintype "passive"))
      (node (ref "U6") (pin "37") (pinfunction "A5_37") (pintype "passive"))
    )
    (net (code "12") (name "/A6") (class "Default")
      (node (ref "CN10") (pin "6") (pinfunction "6_6") (pintype "passive"))
      (node (ref "CN7") (pin "6") (pinfunction "6_6") (pintype "passive"))
      (node (ref "CN8") (pin "6") (pinfunction "6_6") (pintype "passive"))
      (node (ref "CN9") (pin "6") (pinfunction "6_6") (pintype "passive"))
      (node (ref "U6") (pin "38") (pinfunction "A6_38") (pintype "passive"))
    )
    (net (code "13") (name "/A7") (class "Default")
      (node (ref "CN10") (pin "8") (pinfunction "8_8") (pintype "passive"))
      (node (ref "CN7") (pin "8") (pinfunction "8_8") (pintype "passive"))
      (node (ref "CN8") (pin "8") (pinfunction "8_8") (pintype "passive"))
      (node (ref "CN9") (pin "8") (pinfunction "8_8") (pintype "passive"))
      (node (ref "U6") (pin "39") (pinfunction "A7_39") (pintype "passive"))
    )
    (net (code "14") (name "/B0") (class "Default")
      (node (ref "CN14") (pin "2") (pinfunction "2_2") (pintype "passive"))
      (node (ref "CN18") (pin "2") (pinfunction "2_2") (pintype "passive"))
      (node (ref "CN19") (pin "2") (pinfunction "2_2") (pintype "passive"))
      (node (ref "CN20") (pin "2") (pinfunction "2_2") (pintype "passive"))
      (node (ref "U6") (pin "42") (pinfunction "B0_42") (pintype "passive"))
    )
    (net (code "15") (name "/B1") (class "Default")
      (node (ref "CN14") (pin "3") (pinfunction "3_3") (pintype "passive"))
      (node (ref "CN18") (pin "3") (pinfunction "3_3") (pintype "passive"))
      (node (ref "CN19") (pin "3") (pinfunction "3_3") (pintype "passive"))
      (node (ref "CN20") (pin "3") (pinfunction "3_3") (pintype "passive"))
      (node (ref "U6") (pin "43") (pinfunction "B1_43") (pintype "passive"))
    )
    (net (code "16") (name "/B2") (class "Default")
      (node (ref "CN14") (pin "4") (pinfunction "4_4") (pintype "passive"))
      (node (ref "CN18") (pin "4") (pinfunction "4_4") (pintype "passive"))
      (node (ref "CN19") (pin "4") (pinfunction "4_4") (pintype "passive"))
      (node (ref "CN20") (pin "4") (pinfunction "4_4") (pintype "passive"))
      (node (ref "U6") (pin "44") (pinfunction "B2_44") (pintype "passive"))
    )
    (net (code "17") (name "/BUZZER") (class "Default")
      (node (ref "R15") (pin "1") (pinfunction "1_1") (pintype "passive"))
      (node (ref "U6") (pin "85") (pinfunction "G8_85") (pintype "passive"))
    )
    (net (code "18") (name "/C0") (class "Default")
      (node (ref "CN13") (pin "4") (pinfunction "4_4") (pintype "passive"))
      (node (ref "CN15") (pin "4") (pinfunction "4_4") (pintype "passive"))
      (node (ref "CN5") (pin "4") (pinfunction "4_4") (pintype "passive"))
      (node (ref "CN6") (pin "4") (pinfunction "4_4") (pintype "passive"))
      (node (ref "U6") (pin "28") (pinfunction "C0_28") (pintype "passive"))
    )
    (net (code "19") (name "/C1") (class "Default")
      (node (ref "CN13") (pin "7") (pinfunction "7_7") (pintype "passive"))
      (node (ref "CN15") (pin "7") (pinfunction "7_7") (pintype "passive"))
      (node (ref "CN5") (pin "7") (pinfunction "7_7") (pintype "passive"))
      (node (ref "CN6") (pin "7") (pinfunction "7_7") (pintype "passive"))
      (node (ref "U6") (pin "29") (pinfunction "C1_29") (pintype "passive"))
    )
    (net (code "20") (name "/C2") (class "Default")
      (node (ref "CN13") (pin "6") (pinfunction "6_6") (pintype "passive"))
      (node (ref "CN15") (pin "6") (pinfunction "6_6") (pintype "passive"))
      (node (ref "CN5") (pin "6") (pinfunction "6_6") (pintype "passive"))
      (node (ref "CN6") (pin "6") (pinfunction "6_6") (pintype "passive"))
      (node (ref "U6") (pin "30") (pinfunction "C2_30") (pintype "passive"))
    )
    (net (code "21") (name "/C3") (class "Default")
      (node (ref "CN10") (pin "1") (pinfunction "1_1") (pintype "passive"))
      (node (ref "CN7") (pin "1") (pinfunction "1_1") (pintype "passive"))
      (node (ref "CN8") (pin "1") (pinfunction "1_1") (pintype "passive"))
      (node (ref "CN9") (pin "1") (pinfunction "1_1") (pintype "passive"))
      (node (ref "U6") (pin "31") (pinfunction "C3_31") (pintype "passive"))
    )
    (net (code "22") (name "/C5") (class "Default")
      (node (ref "CN14") (pin "1") (pinfunction "1_1") (pintype "passive"))
      (node (ref "CN18") (pin "1") (pinfunction "1_1") (pintype "passive"))
      (node (ref "CN19") (pin "1") (pinfunction "1_1") (pintype "passive"))
      (node (ref "CN20") (pin "1") (pinfunction "1_1") (pintype "passive"))
      (node (ref "U6") (pin "41") (pinfunction "C5_41") (pintype "passive"))
    )
    (net (code "23") (name "/CANH") (class "Default")
      (node (ref "R12") (pin "2") (pinfunction "2_2") (pintype "passive"))
      (node (ref "U3") (pin "1") (pinfunction "1_1") (pintype "passive"))
      (node (ref "U4") (pin "1") (pinfunction "1_1") (pintype "passive"))
      (node (ref "U5") (pin "7") (pinfunction "CANH_7") (pintype "passive"))
    )
    (net (code "24") (name "/CANL") (class "Default")
      (node (ref "R12") (pin "1") (pinfunction "1_1") (pintype "passive"))
      (node (ref "U3") (pin "2") (pinfunction "2_2") (pintype "passive"))
      (node (ref "U4") (pin "2") (pinfunction "2_2") (pintype "passive"))
      (node (ref "U5") (pin "6") (pinfunction "CANL_6") (pintype "passive"))
    )
    (net (code "25") (name "/CANRX") (class "Default")
      (node (ref "U5") (pin "1") (pinfunction "TXD_1") (pintype "passive"))
      (node (ref "U6") (pin "121") (pinfunction "B8_121") (pintype "passive"))
    )
    (net (code "26") (name "/CANTX") (class "Default")
      (node (ref "U5") (pin "4") (pinfunction "RXD_4") (pintype "passive"))
      (node (ref "U6") (pin "122") (pinfunction "B9_122") (pintype "passive"))
    )
    (net (code "27") (name "/CLK0") (class "Default")
      (node (ref "U10") (pin "1") (pinfunction "CLKIN_1") (pintype "passive"))
      (node (ref "U8") (pin "10") (pinfunction "CLK0_10") (pintype "passive"))
    )
    (net (code "28") (name "/CLK1") (class "Default")
      (node (ref "U8") (pin "9") (pinfunction "CLK1_9") (pintype "passive"))
    )
    (net (code "29") (name "/CLK2") (class "Default")
      (node (ref "U8") (pin "6") (pinfunction "CLK2_6") (pintype "passive"))
    )
    (net (code "30") (name "/CLKBUF_EN") (class "Default")
      (node (ref "R19") (pin "1") (pinfunction "1_1") (pintype "passive"))
      (node (ref "U10") (pin "2") (pinfunction "1G_2") (pintype "passive"))
      (node (ref "U6") (pin "77") (pinfunction "G2_77") (pintype "passive"))
    )
    (net (code "31") (name "/CLK_0") (class "Default")
      (node (ref "R22") (pin "2") (pinfunction "2_2") (pintype "passive"))
      (node (ref "RF1") (pin "5") (pinfunction "IN_5") (pintype "passive"))
    )
    (net (code "32") (name "/CLK_1") (class "Default")
      (node (ref "R18") (pin "2") (pinfunction "2_2") (pintype "passive"))
      (node (ref "RF2") (pin "5") (pinfunction "IN_5") (pintype "passive"))
    )
    (net (code "33") (name "/CLK_2") (class "Default")
      (node (ref "R23") (pin "1") (pinfunction "1_1") (pintype "passive"))
      (node (ref "RF3") (pin "5") (pinfunction "IN_5") (pintype "passive"))
    )
    (net (code "34") (name "/CLK_3") (class "Default")
      (node (ref "R20") (pin "2") (pinfunction "2_2") (pintype "passive"))
      (node (ref "RF4") (pin "5") (pinfunction "IN_5") (pintype "passive"))
    )
    (net (code "35") (name "/DAC_OUT1") (class "Default")
      (node (ref "CN18") (pin "8") (pinfunction "8_8") (pintype "passive"))
      (node (ref "U9") (pin "9") (pinfunction "VOUTD_9") (pintype "passive"))
    )
    (net (code "36") (name "/DAC_OUT2") (class "Default")
      (node (ref "CN19") (pin "8") (pinfunction "8_8") (pintype "passive"))
      (node (ref "U9") (pin "8") (pinfunction "VOUTC_8") (pintype "passive"))
    )
    (net (code "37") (name "/DAC_OUT3") (class "Default")
      (node (ref "CN20") (pin "8") (pinfunction "8_8") (pintype "passive"))
      (node (ref "U9") (pin "7") (pinfunction "VOUTB_7") (pintype "passive"))
    )
    (net (code "38") (name "/DAC_OUT4") (class "Default")
      (node (ref "CN14") (pin "8") (pinfunction "8_8") (pintype "passive"))
      (node (ref "U9") (pin "6") (pinfunction "VOUTA_6") (pintype "passive"))
    )
    (net (code "39") (name "/DIN") (class "Default")
      (node (ref "CN11") (pin "6") (pinfunction "6_6") (pintype "passive"))
      (node (ref "U6") (pin "68") (pinfunction "B15_68") (pintype "passive"))
    )
    (net (code "40") (name "/DOUT") (class "Default")
      (node (ref "CN17") (pin "5") (pinfunction "5_5") (pintype "passive"))
      (node (ref "U6") (pin "67") (pinfunction "B14_67") (pintype "passive"))
    )
    (net (code "41") (name "/F7") (class "Default")
      (node (ref "CN13") (pin "1") (pinfunction "1_1") (pintype "passive"))
      (node (ref "CN15") (pin "1") (pinfunction "1_1") (pintype "passive"))
      (node (ref "CN5") (pin "1") (pinfunction "1_1") (pintype "passive"))
      (node (ref "CN6") (pin "1") (pinfunction "1_1") (pintype "passive"))
      (node (ref "U6") (pin "24") (pinfunction "F7_24") (pintype "passive"))
    )
    (net (code "42") (name "/F8") (class "Default")
      (node (ref "CN13") (pin "3") (pinfunction "3_3") (pintype "passive"))
      (node (ref "CN15") (pin "3") (pinfunction "3_3") (pintype "passive"))
      (node (ref "CN5") (pin "3") (pinfunction "3_3") (pintype "passive"))
      (node (ref "CN6") (pin "3") (pinfunction "3_3") (pintype "passive"))
      (node (ref "U6") (pin "25") (pinfunction "F8_25") (pintype "passive"))
    )
    (net (code "43") (name "/F9") (class "Default")
      (node (ref "CN13") (pin "2") (pinfunction "2_2") (pintype "passive"))
      (node (ref "CN15") (pin "2") (pinfunction "2_2") (pintype "passive"))
      (node (ref "CN5") (pin "2") (pinfunction "2_2") (pintype "passive"))
      (node (ref "CN6") (pin "2") (pinfunction "2_2") (pintype "passive"))
      (node (ref "U6") (pin "26") (pinfunction "F9_26") (pintype "passive"))
    )
    (net (code "44") (name "/F10") (class "Default")
      (node (ref "CN13") (pin "5") (pinfunction "5_5") (pintype "passive"))
      (node (ref "CN15") (pin "5") (pinfunction "5_5") (pintype "passive"))
      (node (ref "CN5") (pin "5") (pinfunction "5_5") (pintype "passive"))
      (node (ref "CN6") (pin "5") (pinfunction "5_5") (pintype "passive"))
      (node (ref "U6") (pin "27") (pinfunction "F10_27") (pintype "passive"))
    )
    (net (code "45") (name "/F11") (class "Default")
      (node (ref "CN14") (pin "5") (pinfunction "5_5") (pintype "passive"))
      (node (ref "CN18") (pin "5") (pinfunction "5_5") (pintype "passive"))
      (node (ref "CN19") (pin "5") (pinfunction "5_5") (pintype "passive"))
      (node (ref "CN20") (pin "5") (pinfunction "5_5") (pintype "passive"))
      (node (ref "U6") (pin "45") (pinfunction "F11_45") (pintype "passive"))
    )
    (net (code "46") (name "/F12") (class "Default")
      (node (ref "CN14") (pin "6") (pinfunction "6_6") (pintype "passive"))
      (node (ref "CN18") (pin "6") (pinfunction "6_6") (pintype "passive"))
      (node (ref "CN19") (pin "6") (pinfunction "6_6") (pintype "passive"))
      (node (ref "CN20") (pin "6") (pinfunction "6_6") (pintype "passive"))
      (node (ref "U6") (pin "46") (pinfunction "F12_46") (pintype "passive"))
    )
    (net (code "47") (name "/F13") (class "Default")
      (node (ref "CN14") (pin "7") (pinfunction "7_7") (pintype "passive"))
      (node (ref "CN18") (pin "7") (pinfunction "7_7") (pintype "passive"))
      (node (ref "CN19") (pin "7") (pinfunction "7_7") (pintype "passive"))
      (node (ref "CN20") (pin "7") (pinfunction "7_7") (pintype "passive"))
      (node (ref "U6") (pin "47") (pinfunction "F13_47") (pintype "passive"))
    )
    (net (code "48") (name "/LDAC") (class "Default")
      (node (ref "U6") (pin "61") (pinfunction "E14_61") (pintype "passive"))
      (node (ref "U9") (pin "4") (pinfunction "LDAC#_4") (pintype "passive"))
    )
    (net (code "49") (name "/LED1") (class "Default")
      (node (ref "LED1") (pin "1") (pinfunction "A_1") (pintype "passive"))
      (node (ref "U6") (pin "86") (pinfunction "C6_86") (pintype "passive"))
    )
    (net (code "50") (name "/LED2") (class "Default")
      (node (ref "LED2") (pin "1") (pinfunction "A_1") (pintype "passive"))
      (node (ref "U6") (pin "87") (pinfunction "C7_87") (pintype "passive"))
    )
    (net (code "51") (name "/LED3") (class "Default")
      (node (ref "LED3") (pin "1") (pinfunction "A_1") (pintype "passive"))
      (node (ref "U6") (pin "88") (pinfunction "C8_88") (pintype "passive"))
    )
    (net (code "52") (name "/LED4") (class "Default")
      (node (ref "LED4") (pin "1") (pinfunction "A_1") (pintype "passive"))
      (node (ref "U6") (pin "89") (pinfunction "C9_89") (pintype "passive"))
    )
    (net (code "53") (name "/LED5") (class "Default")
      (node (ref "LED5") (pin "1") (pinfunction "A_1") (pintype "passive"))
      (node (ref "U6") (pin "90") (pinfunction "A8_90") (pintype "passive"))
    )
    (net (code "54") (name "/LED6") (class "Default")
      (node (ref "LED6") (pin "1") (pinfunction "A_1") (pintype "passive"))
      (node (ref "U6") (pin "97") (pinfunction "A15_97") (pintype "passive"))
    )
    (net (code "55") (name "/LED7") (class "Default")
      (node (ref "LED7") (pin "1") (pinfunction "A_1") (pintype "passive"))
      (node (ref "U6") (pin "98") (pinfunction "C10_98") (pintype "passive"))
    )
    (net (code "56") (name "/LED8") (class "Default")
      (node (ref "LED8") (pin "1") (pinfunction "A_1") (pintype "passive"))
      (node (ref "U6") (pin "99") (pinfunction "C11_99") (pintype "passive"))
    )
    (net (code "57") (name "/OE") (class "Default")
      (node (ref "CN11") (pin "4") (pinfunction "4_4") (pintype "passive"))
      (node (ref "CN12") (pin "4") (pinfunction "4_4") (pintype "passive"))
      (node (ref "CN16") (pin "4") (pinfunction "4_4") (pintype "passive"))
      (node (ref "CN17") (pin "4") (pinfunction "4_4") (pintype "passive"))
      (node (ref "U6") (pin "70") (pinfunction "D9_70") (pintype "passive"))
    )
    (net (code "58") (name "/RESET1") (class "Default")
      (node (ref "R32") (pin "2") (pinfunction "2_2") (pintype "passive"))
      (node (ref "U12") (pin "4") (pinfunction "RST#_4") (pintype "passive"))
      (node (ref "U6") (pin "105") (pinfunction "D4_105") (pintype "passive"))
    )
    (net (code "59") (name "/RST") (class "Default")
      (node (ref "CN11") (pin "1") (pinfunction "1_1") (pintype "passive"))
      (node (ref "CN12") (pin "1") (pinfunction "1_1") (pintype "passive"))
      (node (ref "CN16") (pin "1") (pinfunction "1_1") (pintype "passive"))
      (node (ref "CN17") (pin "1") (pinfunction "1_1") (pintype "passive"))
      (node (ref "U6") (pin "48") (pinfunction "F14_48") (pintype "passive"))
    )
    (net (code "60") (name "/RX_U2S") (class "Default")
      (node (ref "U11") (pin "2") (pinfunction "2_2") (pintype "passive"))
      (node (ref "U12") (pin "5") (pinfunction "URX_5") (pintype "passive"))
    )
    (net (code "61") (name "/SCL1") (class "Default")
      (node (ref "R9") (pin "1") (pinfunction "1_1") (pintype "passive"))
      (node (ref "U3") (pin "3") (pinfunction "3_3") (pintype "passive"))
      (node (ref "U4") (pin "3") (pinfunction "3_3") (pintype "passive"))
      (node (ref "U6") (pin "119") (pinfunction "B6_119") (pintype "passive"))
    )
    (net (code "62") (name "/SCL2") (class "Default")
      (node (ref "R13") (pin "1") (pinfunction "1_1") (pintype "passive"))
      (node (ref "U6") (pin "63") (pinfunction "B10_63") (pintype "passive"))
      (node (ref "U7") (pin "2") (pinfunction "2_2") (pintype "passive"))
      (node (ref "U8") (pin "4") (pinfunction "SCL_4") (pintype "passive"))
      (node (ref "U9") (pin "2") (pinfunction "SCL_2") (pintype "passive"))
    )
    (net (code "63") (name "/SCL_U2S") (class "Default")
      (node (ref "U11") (pin "4") (pinfunction "4_4") (pintype "passive"))
      (node (ref "U12") (pin "10") (pinfunction "SCL_10") (pintype "passive"))
    )
    (net (code "64") (name "/SDA1") (class "Default")
      (node (ref "R10") (pin "1") (pinfunction "1_1") (pintype "passive"))
      (node (ref "U3") (pin "4") (pinfunction "4_4") (pintype "passive"))
      (node (ref "U4") (pin "4") (pinfunction "4_4") (pintype "passive"))
      (node (ref "U6") (pin "120") (pinfunction "B7_120") (pintype "passive"))
    )
    (net (code "65") (name "/SDA2") (class "Default")
      (node (ref "R14") (pin "1") (pinfunction "1_1") (pintype "passive"))
      (node (ref "U6") (pin "64") (pinfunction "B11_64") (pintype "passive"))
      (node (ref "U7") (pin "1") (pinfunction "1_1") (pintype "passive"))
      (node (ref "U8") (pin "5") (pinfunction "SDA_5") (pintype "passive"))
      (node (ref "U9") (pin "3") (pinfunction "SDA_3") (pintype "passive"))
    )
    (net (code "66") (name "/SDA_U2S") (class "Default")
      (node (ref "U11") (pin "3") (pinfunction "3_3") (pintype "passive"))
      (node (ref "U12") (pin "9") (pinfunction "SDA_9") (pintype "passive"))
    )
    (net (code "67") (name "/SHCP") (class "Default")
      (node (ref "CN11") (pin "2") (pinfunction "2_2") (pintype "passive"))
      (node (ref "CN12") (pin "2") (pinfunction "2_2") (pintype "passive"))
      (node (ref "CN16") (pin "2") (pinfunction "2_2") (pintype "passive"))
      (node (ref "CN17") (pin "2") (pinfunction "2_2") (pintype "passive"))
      (node (ref "U6") (pin "66") (pinfunction "B13_66") (pintype "passive"))
    )
    (net (code "68") (name "/SPI3_CLK") (class "Default")
      (node (ref "U6") (pin "116") (pinfunction "B3_116") (pintype "passive"))
    )
    (net (code "69") (name "/SPI3_MISO") (class "Default")
      (node (ref "U6") (pin "117") (pinfunction "B4_117") (pintype "passive"))
    )
    (net (code "70") (name "/SPI3_MOSI") (class "Default")
      (node (ref "U6") (pin "118") (pinfunction "B5_118") (pintype "passive"))
    )
    (net (code "71") (name "/STCP") (class "Default")
      (node (ref "CN11") (pin "3") (pinfunction "3_3") (pintype "passive"))
      (node (ref "CN12") (pin "3") (pinfunction "3_3") (pintype "passive"))
      (node (ref "CN16") (pin "3") (pinfunction "3_3") (pintype "passive"))
      (node (ref "CN17") (pin "3") (pinfunction "3_3") (pintype "passive"))
      (node (ref "U6") (pin "69") (pinfunction "D8_69") (pintype "passive"))
    )
    (net (code "72") (name "/SW1") (class "Default")
      (node (ref "C1") (pin "2") (pinfunction "2_2") (pintype "passive"))
      (node (ref "R5") (pin "1") (pinfunction "1_1") (pintype "passive"))
      (node (ref "U6") (pin "100") (pinfunction "C12_100") (pintype "passive"))
    )
    (net (code "73") (name "/SW2") (class "Default")
      (node (ref "C2") (pin "2") (pinfunction "2_2") (pintype "passive"))
      (node (ref "R6") (pin "1") (pinfunction "1_1") (pintype "passive"))
      (node (ref "U6") (pin "102") (pinfunction "D1_102") (pintype "passive"))
    )
    (net (code "74") (name "/SW3") (class "Default")
      (node (ref "C3") (pin "2") (pinfunction "2_2") (pintype "passive"))
      (node (ref "R7") (pin "1") (pinfunction "1_1") (pintype "passive"))
      (node (ref "U6") (pin "101") (pinfunction "D0_101") (pintype "passive"))
    )
    (net (code "75") (name "/SW4") (class "Default")
      (node (ref "C4") (pin "2") (pinfunction "2_2") (pintype "passive"))
      (node (ref "R8") (pin "1") (pinfunction "1_1") (pintype "passive"))
      (node (ref "U6") (pin "103") (pinfunction "D2_103") (pintype "passive"))
    )
    (net (code "76") (name "/TX_U2S") (class "Default")
      (node (ref "U11") (pin "1") (pinfunction "1_1") (pintype "passive"))
      (node (ref "U12") (pin "6") (pinfunction "UTX_6") (pintype "passive"))
    )
    (net (code "77") (name "/U2S_D+") (class "Default")
      (node (ref "CN3") (pin "3") (pinfunction "D+_3") (pintype "passive"))
      (node (ref "U12") (pin "13") (pinfunction "D+_13") (pintype "passive"))
    )
    (net (code "78") (name "/U2S_D-") (class "Default")
      (node (ref "CN3") (pin "2") (pinfunction "D-_2") (pintype "passive"))
      (node (ref "U12") (pin "12") (pinfunction "D-_12") (pintype "passive"))
    )
    (net (code "79") (name "/UART1_RX") (class "Default")
      (node (ref "H5") (pin "2") (pinfunction "2_2") (pintype "passive"))
      (node (ref "U6") (pin "92") (pinfunction "A10_92") (pintype "passive"))
    )
    (net (code "80") (name "/UART1_TX") (class "Default")
      (node (ref "H5") (pin "1") (pinfunction "1_1") (pintype "passive"))
      (node (ref "U6") (pin "91") (pinfunction "A9_91") (pintype "passive"))
    )
    (net (code "81") (name "/USB_D+") (class "Default")
      (node (ref "R17") (pin "1") (pinfunction "1_1") (pintype "passive"))
      (node (ref "U6") (pin "94") (pinfunction "A12_94") (pintype "passive"))
    )
    (net (code "82") (name "/USB_D-") (class "Default")
      (node (ref "R16") (pin "2") (pinfunction "2_2") (pintype "passive"))
      (node (ref "U6") (pin "93") (pinfunction "A11_93") (pintype "passive"))
    )
    (net (code "83") (name "/XA") (class "Default")
      (node (ref "U8") (pin "2") (pinfunction "XA_2") (pintype "passive"))
      (node (ref "X1") (pin "3") (pinfunction "OSC2_3") (pintype "passive"))
    )
    (net (code "84") (name "/XB") (class "Default")
      (node (ref "U8") (pin "3") (pinfunction "XB_3") (pintype "passive"))
      (node (ref "X1") (pin "1") (pinfunction "OSC1_1") (pintype "passive"))
    )
    (net (code "85") (name "GND") (class "Default")
      (node (ref "C1") (pin "1") (pinfunction "1_1") (pintype "passive"))
      (node (ref "C10") (pin "1") (pinfunction "1_1") (pintype "passive"))
      (node (ref "C11") (pin "1") (pinfunction "1_1") (pintype "passive"))
      (node (ref "C12") (pin "1") (pinfunction "1_1") (pintype "passive"))
      (node (ref "C13") (pin "2") (pinfunction "2_2") (pintype "passive"))
      (node (ref "C14") (pin "1") (pinfunction "1_1") (pintype "passive"))
      (node (ref "C15") (pin "1") (pinfunction "1_1") (pintype "passive"))
      (node (ref "C2") (pin "1") (pinfunction "1_1") (pintype "passive"))
      (node (ref "C3") (pin "1") (pinfunction "1_1") (pintype "passive"))
      (node (ref "C4") (pin "1") (pinfunction "1_1") (pintype "passive"))
      (node (ref "C5") (pin "1") (pinfunction "1_1") (pintype "passive"))
      (node (ref "C6") (pin "2") (pinfunction "2_2") (pintype "passive"))
      (node (ref "C7") (pin "1") (pinfunction "1_1") (pintype "passive"))
      (node (ref "C8") (pin "1") (pinfunction "1_1") (pintype "passive"))
      (node (ref "C9") (pin "1") (pinfunction "1_1") (pintype "passive"))
      (node (ref "CN1") (pin "1") (pinfunction "1_1") (pintype "passive"))
      (node (ref "CN1") (pin "2") (pinfunction "2_2") (pintype "passive"))
      (node (ref "CN2") (pin "4") (pinfunction "GND_4") (pintype "passive"))
      (node (ref "CN3") (pin "4") (pinfunction "GND_4") (pintype "passive"))
      (node (ref "H1") (pin "2") (pinfunction "2_2") (pintype "passive"))
      (node (ref "H2") (pin "2") (pinfunction "2_2") (pintype "passive"))
      (node (ref "H3") (pin "2") (pinfunction "2_2") (pintype "passive"))
      (node (ref "H4") (pin "2") (pinfunction "2_2") (pintype "passive"))
      (node (ref "Q1") (pin "2") (pinfunction "2_2") (pintype "passive"))
      (node (ref "R11") (pin "2") (pinfunction "2_2") (pintype "passive"))
      (node (ref "R24") (pin "2") (pinfunction "2_2") (pintype "passive"))
      (node (ref "R25") (pin "2") (pinfunction "2_2") (pintype "passive"))
      (node (ref "R26") (pin "2") (pinfunction "2_2") (pintype "passive"))
      (node (ref "R27") (pin "2") (pinfunction "2_2") (pintype "passive"))
      (node (ref "R28") (pin "2") (pinfunction "2_2") (pintype "passive"))
      (node (ref "R29") (pin "2") (pinfunction "2_2") (pintype "passive"))
      (node (ref "R30") (pin "2") (pinfunction "2_2") (pintype "passive"))
      (node (ref "R31") (pin "2") (pinfunction "2_2") (pintype "passive"))
      (node (ref "RF1") (pin "1") (pinfunction "GND_1") (pintype "passive"))
      (node (ref "RF1") (pin "2") (pinfunction "GND_2") (pintype "passive"))
      (node (ref "RF1") (pin "3") (pinfunction "GND_3") (pintype "passive"))
      (node (ref "RF1") (pin "4") (pinfunction "GND_4") (pintype "passive"))
      (node (ref "RF2") (pin "1") (pinfunction "GND_1") (pintype "passive"))
      (node (ref "RF2") (pin "2") (pinfunction "GND_2") (pintype "passive"))
      (node (ref "RF2") (pin "3") (pinfunction "GND_3") (pintype "passive"))
      (node (ref "RF2") (pin "4") (pinfunction "GND_4") (pintype "passive"))
      (node (ref "RF3") (pin "1") (pinfunction "GND_1") (pintype "passive"))
      (node (ref "RF3") (pin "2") (pinfunction "GND_2") (pintype "passive"))
      (node (ref "RF3") (pin "3") (pinfunction "GND_3") (pintype "passive"))
      (node (ref "RF3") (pin "4") (pinfunction "GND_4") (pintype "passive"))
      (node (ref "RF4") (pin "1") (pinfunction "GND_1") (pintype "passive"))
      (node (ref "RF4") (pin "2") (pinfunction "GND_2") (pintype "passive"))
      (node (ref "RF4") (pin "3") (pinfunction "GND_3") (pintype "passive"))
      (node (ref "RF4") (pin "4") (pinfunction "GND_4") (pintype "passive"))
      (node (ref "U10") (pin "4") (pinfunction "GND_4") (pintype "passive"))
      (node (ref "U12") (pin "14") (pinfunction "VSS_14") (pintype "passive"))
      (node (ref "U2") (pin "2") (pinfunction "2_2") (pintype "passive"))
      (node (ref "U3") (pin "5") (pinfunction "5_5") (pintype "passive"))
      (node (ref "U4") (pin "5") (pinfunction "5_5") (pintype "passive"))
      (node (ref "U5") (pin "2") (pinfunction "VSS_2") (pintype "passive"))
      (node (ref "U6") (pin "125") (pinfunction "GND_125") (pintype "passive"))
      (node (ref "U6") (pin "126") (pinfunction "GND_126") (pintype "passive"))
      (node (ref "U6") (pin "13") (pinfunction "GND_13") (pintype "passive"))
      (node (ref "U6") (pin "14") (pinfunction "GND_14") (pintype "passive"))
      (node (ref "U6") (pin "55") (pinfunction "GND_55") (pintype "passive"))
      (node (ref "U6") (pin "56") (pinfunction "GND_56") (pintype "passive"))
      (node (ref "U6") (pin "83") (pinfunction "GND_83") (pintype "passive"))
      (node (ref "U6") (pin "84") (pinfunction "GND_84") (pintype "passive"))
      (node (ref "U7") (pin "4") (pinfunction "4_4") (pintype "passive"))
      (node (ref "U8") (pin "8") (pinfunction "GND_8") (pintype "passive"))
      (node (ref "U9") (pin "10") (pinfunction "VSS_10") (pintype "passive"))
      (node (ref "X1") (pin "2") (pinfunction "GND_2") (pintype "passive"))
      (node (ref "X1") (pin "4") (pinfunction "GND_4") (pintype "passive"))
    )
    (net (code "86") (name "Net-(BUZZER1--)") (class "Default")
      (node (ref "BUZZER1") (pin "2") (pinfunction "-_2") (pintype "passive"))
      (node (ref "Q1") (pin "3") (pinfunction "3_3") (pintype "passive"))
    )
    (net (code "87") (name "Net-(CN2-D+)") (class "Default")
      (node (ref "CN2") (pin "3") (pinfunction "D+_3") (pintype "passive"))
      (node (ref "R17") (pin "2") (pinfunction "2_2") (pintype "passive"))
    )
    (net (code "88") (name "Net-(CN2-D-)") (class "Default")
      (node (ref "CN2") (pin "2") (pinfunction "D-_2") (pintype "passive"))
      (node (ref "R16") (pin "1") (pinfunction "1_1") (pintype "passive"))
    )
    (net (code "89") (name "Net-(CN2-VCC)") (class "Default")
      (node (ref "CN2") (pin "1") (pinfunction "VCC_1") (pintype "passive"))
      (node (ref "D1") (pin "2") (pinfunction "A_2") (pintype "passive"))
    )
    (net (code "90") (name "Net-(H1-Pad1)") (class "Default")
      (node (ref "H1") (pin "1") (pinfunction "1_1") (pintype "passive"))
      (node (ref "R1") (pin "1") (pinfunction "1_1") (pintype "passive"))
      (node (ref "R5") (pin "2") (pinfunction "2_2") (pintype "passive"))
    )
    (net (code "91") (name "Net-(H2-Pad1)") (class "Default")
      (node (ref "H2") (pin "1") (pinfunction "1_1") (pintype "passive"))
      (node (ref "R2") (pin "1") (pinfunction "1_1") (pintype "passive"))
      (node (ref "R6") (pin "2") (pinfunction "2_2") (pintype "passive"))
    )
    (net (code "92") (name "Net-(H3-Pad1)") (class "Default")
      (node (ref "H3") (pin "1") (pinfunction "1_1") (pintype "passive"))
      (node (ref "R3") (pin "1") (pinfunction "1_1") (pintype "passive"))
      (node (ref "R7") (pin "2") (pinfunction "2_2") (pintype "passive"))
    )
    (net (code "93") (name "Net-(H4-Pad1)") (class "Default")
      (node (ref "H4") (pin "1") (pinfunction "1_1") (pintype "passive"))
      (node (ref "R4") (pin "1") (pinfunction "1_1") (pintype "passive"))
      (node (ref "R8") (pin "2") (pinfunction "2_2") (pintype "passive"))
    )
    (net (code "94") (name "Net-(LED1-K)") (class "Default")
      (node (ref "LED1") (pin "2") (pinfunction "K_2") (pintype "passive"))
      (node (ref "R24") (pin "1") (pinfunction "1_1") (pintype "passive"))
    )
    (net (code "95") (name "Net-(LED2-K)") (class "Default")
      (node (ref "LED2") (pin "2") (pinfunction "K_2") (pintype "passive"))
      (node (ref "R25") (pin "1") (pinfunction "1_1") (pintype "passive"))
    )
    (net (code "96") (name "Net-(LED3-K)") (class "Default")
      (node (ref "LED3") (pin "2") (pinfunction "K_2") (pintype "passive"))
      (node (ref "R26") (pin "1") (pinfunction "1_1") (pintype "passive"))
    )
    (net (code "97") (name "Net-(LED4-K)") (class "Default")
      (node (ref "LED4") (pin "2") (pinfunction "K_2") (pintype "passive"))
      (node (ref "R27") (pin "1") (pinfunction "1_1") (pintype "passive"))
    )
    (net (code "98") (name "Net-(LED5-C)") (class "Default")
      (node (ref "LED5") (pin "2") (pinfunction "C_2") (pintype "passive"))
      (node (ref "R28") (pin "1") (pinfunction "1_1") (pintype "passive"))
    )
    (net (code "99") (name "Net-(LED6-C)") (class "Default")
      (node (ref "LED6") (pin "2") (pinfunction "C_2") (pintype "passive"))
      (node (ref "R29") (pin "1") (pinfunction "1_1") (pintype "passive"))
    )
    (net (code "100") (name "Net-(LED7-K)") (class "Default")
      (node (ref "LED7") (pin "2") (pinfunction "K_2") (pintype "passive"))
      (node (ref "R30") (pin "1") (pinfunction "1_1") (pintype "passive"))
    )
    (net (code "101") (name "Net-(LED8-K)") (class "Default")
      (node (ref "LED8") (pin "2") (pinfunction "K_2") (pintype "passive"))
      (node (ref "R31") (pin "1") (pinfunction "1_1") (pintype "passive"))
    )
    (net (code "102") (name "Net-(Q1-Pad1)") (class "Default")
      (node (ref "Q1") (pin "1") (pinfunction "1_1") (pintype "passive"))
      (node (ref "R15") (pin "2") (pinfunction "2_2") (pintype "passive"))
    )
    (net (code "103") (name "Net-(U5-RS)") (class "Default")
      (node (ref "R11") (pin "1") (pinfunction "1_1") (pintype "passive"))
      (node (ref "U5") (pin "8") (pinfunction "RS_8") (pintype "passive"))
    )
    (net (code "104") (name "Net-(U10-Y0)") (class "Default")
      (node (ref "R22") (pin "1") (pinfunction "1_1") (pintype "passive"))
      (node (ref "U10") (pin "3") (pinfunction "Y0_3") (pintype "passive"))
    )
    (net (code "105") (name "Net-(U10-Y1)") (class "Default")
      (node (ref "R18") (pin "1") (pinfunction "1_1") (pintype "passive"))
      (node (ref "U10") (pin "8") (pinfunction "Y1_8") (pintype "passive"))
    )
    (net (code "106") (name "Net-(U10-Y2)") (class "Default")
      (node (ref "R23") (pin "2") (pinfunction "2_2") (pintype "passive"))
      (node (ref "U10") (pin "5") (pinfunction "Y2_5") (pintype "passive"))
    )
    (net (code "107") (name "Net-(U10-Y3)") (class "Default")
      (node (ref "R20") (pin "1") (pinfunction "1_1") (pintype "passive"))
      (node (ref "U10") (pin "7") (pinfunction "Y3_7") (pintype "passive"))
    )
    (net (code "108") (name "unconnected-(CN2-EH-Pad5)") (class "Default")
      (node (ref "CN2") (pin "5") (pinfunction "EH_5") (pintype "passive"))
    )
    (net (code "109") (name "unconnected-(CN2-EH-Pad5)_1") (class "Default")
      (node (ref "CN2") (pin "5") (pinfunction "EH_5") (pintype "passive"))
    )
    (net (code "110") (name "unconnected-(CN3-EH-Pad5)") (class "Default")
      (node (ref "CN3") (pin "5") (pinfunction "EH_5") (pintype "passive"))
    )
    (net (code "111") (name "unconnected-(CN3-EH-Pad5)_1") (class "Default")
      (node (ref "CN3") (pin "5") (pinfunction "EH_5") (pintype "passive"))
    )
    (net (code "112") (name "unconnected-(CN3-VCC-Pad1)") (class "Default")
      (node (ref "CN3") (pin "1") (pinfunction "VCC_1") (pintype "passive"))
    )
    (net (code "113") (name "unconnected-(R21-Pad1)") (class "Default")
      (node (ref "R21") (pin "1") (pinfunction "1_1") (pintype "passive"))
    )
    (net (code "114") (name "unconnected-(R21-Pad2)") (class "Default")
      (node (ref "R21") (pin "2") (pinfunction "2_2") (pintype "passive"))
    )
    (net (code "115") (name "unconnected-(U1-Pad2)") (class "Default")
      (node (ref "U1") (pin "2") (pinfunction "2_2") (pintype "passive"))
    )
    (net (code "116") (name "unconnected-(U3-Pad6)") (class "Default")
      (node (ref "U3") (pin "6") (pinfunction "6_6") (pintype "passive+no_connect"))
    )
    (net (code "117") (name "unconnected-(U4-Pad6)") (class "Default")
      (node (ref "U4") (pin "6") (pinfunction "6_6") (pintype "passive+no_connect"))
    )
    (net (code "118") (name "unconnected-(U5-VREF-Pad5)") (class "Default")
      (node (ref "U5") (pin "5") (pinfunction "VREF_5") (pintype "passive"))
    )
    (net (code "119") (name "unconnected-(U6-3.3-Pad16)") (class "Default")
      (node (ref "U6") (pin "16") (pinfunction "3.3_16") (pintype "passive"))
    )
    (net (code "120") (name "unconnected-(U6-3.3-Pad123)") (class "Default")
      (node (ref "U6") (pin "123") (pinfunction "3.3_123") (pintype "passive"))
    )
    (net (code "121") (name "unconnected-(U6-3.3-Pad124)") (class "Default")
      (node (ref "U6") (pin "124") (pinfunction "3.3_124") (pintype "passive"))
    )
    (net (code "122") (name "unconnected-(U6-A13-Pad95)") (class "Default")
      (node (ref "U6") (pin "95") (pinfunction "A13_95") (pintype "passive"))
    )
    (net (code "123") (name "unconnected-(U6-A14-Pad96)") (class "Default")
      (node (ref "U6") (pin "96") (pinfunction "A14_96") (pintype "passive"))
    )
    (net (code "124") (name "unconnected-(U6-B12-Pad65)") (class "Default")
      (node (ref "U6") (pin "65") (pinfunction "B12_65") (pintype "passive"))
    )
    (net (code "125") (name "unconnected-(U6-C4-Pad40)") (class "Default")
      (node (ref "U6") (pin "40") (pinfunction "C4_40") (pintype "passive+no_connect"))
    )
    (net (code "126") (name "unconnected-(U6-C13-Pad8)") (class "Default")
      (node (ref "U6") (pin "8") (pinfunction "C13_8") (pintype "passive"))
    )
    (net (code "127") (name "unconnected-(U6-C14-Pad9)") (class "Default")
      (node (ref "U6") (pin "9") (pinfunction "C14_9") (pintype "passive"))
    )
    (net (code "128") (name "unconnected-(U6-C15-Pad10)") (class "Default")
      (node (ref "U6") (pin "10") (pinfunction "C15_10") (pintype "passive"))
    )
    (net (code "129") (name "unconnected-(U6-D3-Pad104)") (class "Default")
      (node (ref "U6") (pin "104") (pinfunction "D3_104") (pintype "passive"))
    )
    (net (code "130") (name "unconnected-(U6-D5-Pad106)") (class "Default")
      (node (ref "U6") (pin "106") (pinfunction "D5_106") (pintype "passive"))
    )
    (net (code "131") (name "unconnected-(U6-D6-Pad107)") (class "Default")
      (node (ref "U6") (pin "107") (pinfunction "D6_107") (pintype "passive"))
    )
    (net (code "132") (name "unconnected-(U6-D7-Pad108)") (class "Default")
      (node (ref "U6") (pin "108") (pinfunction "D7_108") (pintype "passive"))
    )
    (net (code "133") (name "unconnected-(U6-D10-Pad71)") (class "Default")
      (node (ref "U6") (pin "71") (pinfunction "D10_71") (pintype "passive"))
    )
    (net (code "134") (name "unconnected-(U6-D11-Pad72)") (class "Default")
      (node (ref "U6") (pin "72") (pinfunction "D11_72") (pintype "passive"))
    )
    (net (code "135") (name "unconnected-(U6-D12-Pad73)") (class "Default")
      (node (ref "U6") (pin "73") (pinfunction "D12_73") (pintype "passive"))
    )
    (net (code "136") (name "unconnected-(U6-D13-Pad74)") (class "Default")
      (node (ref "U6") (pin "74") (pinfunction "D13_74") (pintype "passive"))
    )
    (net (code "137") (name "unconnected-(U6-D14-Pad75)") (class "Default")
      (node (ref "U6") (pin "75") (pinfunction "D14_75") (pintype "passive"))
    )
    (net (code "138") (name "unconnected-(U6-D15-Pad76)") (class "Default")
      (node (ref "U6") (pin "76") (pinfunction "D15_76") (pintype "passive"))
    )
    (net (code "139") (name "unconnected-(U6-E0-Pad1)") (class "Default")
      (node (ref "U6") (pin "1") (pinfunction "E0_1") (pintype "passive"))
    )
    (net (code "140") (name "unconnected-(U6-E1-Pad2)") (class "Default")
      (node (ref "U6") (pin "2") (pinfunction "E1_2") (pintype "passive"))
    )
    (net (code "141") (name "unconnected-(U6-E2-Pad3)") (class "Default")
      (node (ref "U6") (pin "3") (pinfunction "E2_3") (pintype "passive"))
    )
    (net (code "142") (name "unconnected-(U6-E3-Pad4)") (class "Default")
      (node (ref "U6") (pin "4") (pinfunction "E3_4") (pintype "passive"))
    )
    (net (code "143") (name "unconnected-(U6-E4-Pad5)") (class "Default")
      (node (ref "U6") (pin "5") (pinfunction "E4_5") (pintype "passive"))
    )
    (net (code "144") (name "unconnected-(U6-E5-Pad6)") (class "Default")
      (node (ref "U6") (pin "6") (pinfunction "E5_6") (pintype "passive"))
    )
    (net (code "145") (name "unconnected-(U6-E6-Pad7)") (class "Default")
      (node (ref "U6") (pin "7") (pinfunction "E6_7") (pintype "passive"))
    )
    (net (code "146") (name "unconnected-(U6-E7-Pad52)") (class "Default")
      (node (ref "U6") (pin "52") (pinfunction "E7_52") (pintype "passive"))
    )
    (net (code "147") (name "unconnected-(U6-E8-Pad53)") (class "Default")
      (node (ref "U6") (pin "53") (pinfunction "E8_53") (pintype "passive"))
    )
    (net (code "148") (name "unconnected-(U6-E9-Pad54)") (class "Default")
      (node (ref "U6") (pin "54") (pinfunction "E9_54") (pintype "passive"))
    )
    (net (code "149") (name "unconnected-(U6-E10-Pad57)") (class "Default")
      (node (ref "U6") (pin "57") (pinfunction "E10_57") (pintype "passive"))
    )
    (net (code "150") (name "unconnected-(U6-E11-Pad58)") (class "Default")
      (node (ref "U6") (pin "58") (pinfunction "E11_58") (pintype "passive"))
    )
    (net (code "151") (name "unconnected-(U6-E12-Pad59)") (class "Default")
      (node (ref "U6") (pin "59") (pinfunction "E12_59") (pintype "passive"))
    )
    (net (code "152") (name "unconnected-(U6-E13-Pad60)") (class "Default")
      (node (ref "U6") (pin "60") (pinfunction "E13_60") (pintype "passive"))
    )
    (net (code "153") (name "unconnected-(U6-E15-Pad62)") (class "Default")
      (node (ref "U6") (pin "62") (pinfunction "E15_62") (pintype "passive"))
    )
    (net (code "154") (name "unconnected-(U6-F0-Pad11)") (class "Default")
      (node (ref "U6") (pin "11") (pinfunction "F0_11") (pintype "passive"))
    )
    (net (code "155") (name "unconnected-(U6-F1-Pad12)") (class "Default")
      (node (ref "U6") (pin "12") (pinfunction "F1_12") (pintype "passive"))
    )
    (net (code "156") (name "unconnected-(U6-F2-Pad19)") (class "Default")
      (node (ref "U6") (pin "19") (pinfunction "F2_19") (pintype "passive"))
    )
    (net (code "157") (name "unconnected-(U6-F3-Pad20)") (class "Default")
      (node (ref "U6") (pin "20") (pinfunction "F3_20") (pintype "passive"))
    )
    (net (code "158") (name "unconnected-(U6-F4-Pad21)") (class "Default")
      (node (ref "U6") (pin "21") (pinfunction "F4_21") (pintype "passive"))
    )
    (net (code "159") (name "unconnected-(U6-F5-Pad22)") (class "Default")
      (node (ref "U6") (pin "22") (pinfunction "F5_22") (pintype "passive"))
    )
    (net (code "160") (name "unconnected-(U6-F6-Pad23)") (class "Default")
      (node (ref "U6") (pin "23") (pinfunction "F6_23") (pintype "passive"))
    )
    (net (code "161") (name "unconnected-(U6-F15-Pad49)") (class "Default")
      (node (ref "U6") (pin "49") (pinfunction "F15_49") (pintype "passive"))
    )
    (net (code "162") (name "unconnected-(U6-G0-Pad50)") (class "Default")
      (node (ref "U6") (pin "50") (pinfunction "G0_50") (pintype "passive"))
    )
    (net (code "163") (name "unconnected-(U6-G1-Pad51)") (class "Default")
      (node (ref "U6") (pin "51") (pinfunction "G1_51") (pintype "passive"))
    )
    (net (code "164") (name "unconnected-(U6-G3-Pad78)") (class "Default")
      (node (ref "U6") (pin "78") (pinfunction "G3_78") (pintype "passive"))
    )
    (net (code "165") (name "unconnected-(U6-G4-Pad79)") (class "Default")
      (node (ref "U6") (pin "79") (pinfunction "G4_79") (pintype "passive"))
    )
    (net (code "166") (name "unconnected-(U6-G5-Pad80)") (class "Default")
      (node (ref "U6") (pin "80") (pinfunction "G5_80") (pintype "passive"))
    )
    (net (code "167") (name "unconnected-(U6-G6-Pad81)") (class "Default")
      (node (ref "U6") (pin "81") (pinfunction "G6_81") (pintype "passive"))
    )
    (net (code "168") (name "unconnected-(U6-G7-Pad82)") (class "Default")
      (node (ref "U6") (pin "82") (pinfunction "G7_82") (pintype "passive"))
    )
    (net (code "169") (name "unconnected-(U6-G9-Pad109)") (class "Default")
      (node (ref "U6") (pin "109") (pinfunction "G9_109") (pintype "passive"))
    )
    (net (code "170") (name "unconnected-(U6-G10-Pad110)") (class "Default")
      (node (ref "U6") (pin "110") (pinfunction "G10_110") (pintype "passive"))
    )
    (net (code "171") (name "unconnected-(U6-G11-Pad111)") (class "Default")
      (node (ref "U6") (pin "111") (pinfunction "G11_111") (pintype "passive"))
    )
    (net (code "172") (name "unconnected-(U6-G12-Pad112)") (class "Default")
      (node (ref "U6") (pin "112") (pinfunction "G12_112") (pintype "passive"))
    )
    (net (code "173") (name "unconnected-(U6-G13-Pad113)") (class "Default")
      (node (ref "U6") (pin "113") (pinfunction "G13_113") (pintype "passive"))
    )
    (net (code "174") (name "unconnected-(U6-G14-Pad114)") (class "Default")
      (node (ref "U6") (pin "114") (pinfunction "G14_114") (pintype "passive"))
    )
    (net (code "175") (name "unconnected-(U6-G15-Pad115)") (class "Default")
      (node (ref "U6") (pin "115") (pinfunction "G15_115") (pintype "passive+no_connect"))
    )
    (net (code "176") (name "unconnected-(U6-VB-Pad15)") (class "Default")
      (node (ref "U6") (pin "15") (pinfunction "VB_15") (pintype "passive"))
    )
    (net (code "177") (name "unconnected-(U9-RDY{slash}BSY#-Pad5)") (class "Default")
      (node (ref "U9") (pin "5") (pinfunction "RDY/BSY#_5") (pintype "passive"))
    )
    (net (code "178") (name "unconnected-(U12-GP0-Pad2)") (class "Default")
      (node (ref "U12") (pin "2") (pinfunction "GP0_2") (pintype "passive"))
    )
    (net (code "179") (name "unconnected-(U12-GP1-Pad3)") (class "Default")
      (node (ref "U12") (pin "3") (pinfunction "GP1_3") (pintype "passive"))
    )
    (net (code "180") (name "unconnected-(U12-GP2-Pad7)") (class "Default")
      (node (ref "U12") (pin "7") (pinfunction "GP2_7") (pintype "passive"))
    )
    (net (code "181") (name "unconnected-(U12-GP3-Pad8)") (class "Default")
      (node (ref "U12") (pin "8") (pinfunction "GP3_8") (pintype "passive"))
    )
  )
)
